# SOTB_Feb22.net
KiCad netlist of a schematic drawn in EAGLE
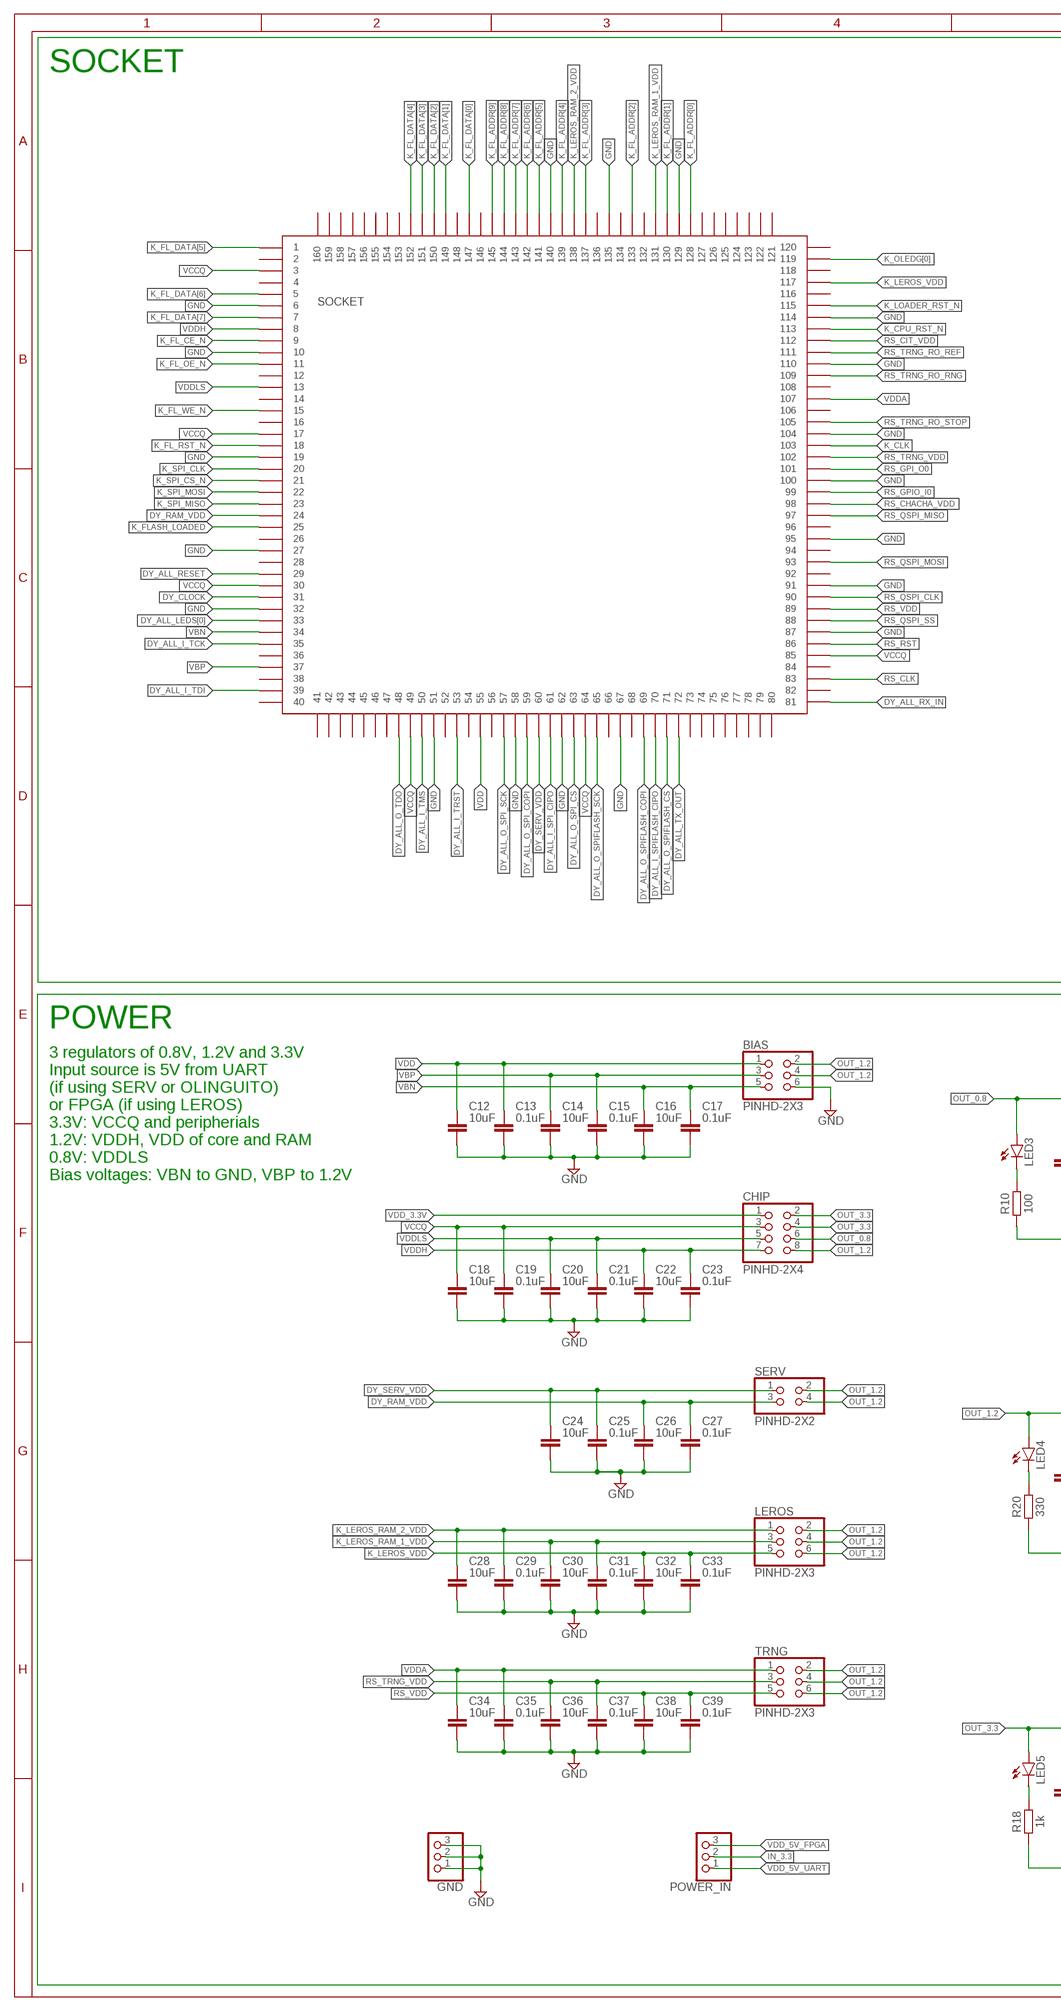
[diagram p0: schematic, sheet 1, part 1 of 2]
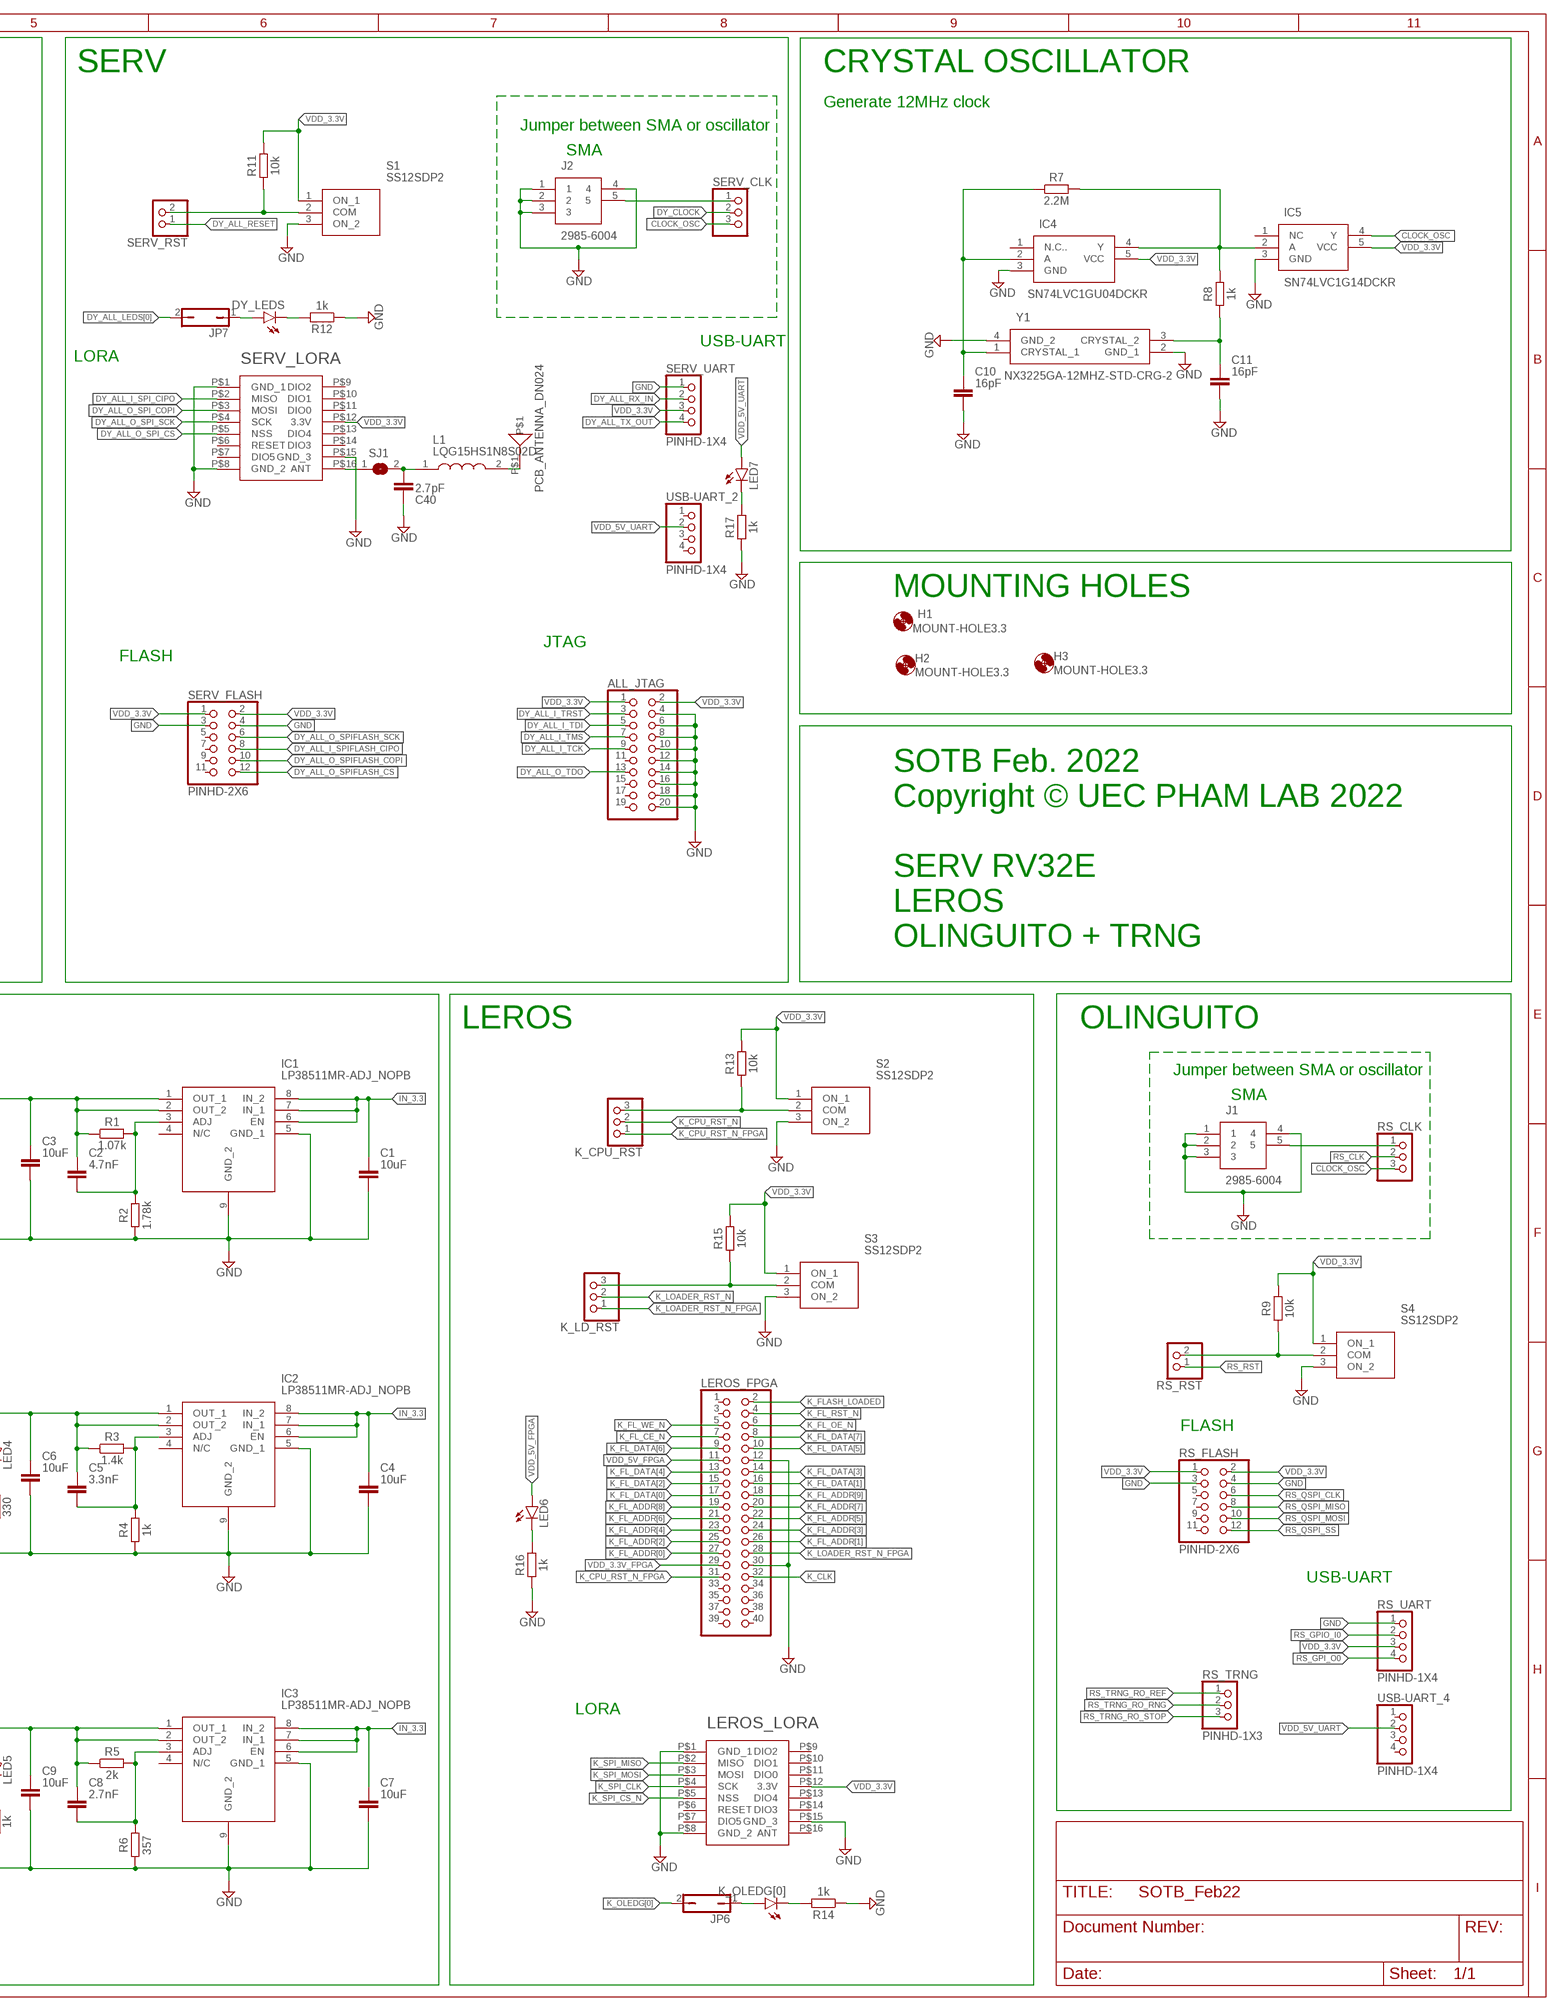
[diagram p1: schematic, sheet 1, part 2 of 2]

(export (version "E")
  (design (tool "Eeschema 10.0.6"))
  (components
    (comp (ref "ALL_JTAG")
      (value "PINHD-2X10")
      (footprint "eagle-import:2X10")
      (libsource (lib "eagle-import") (part "PINHD-2X10"))
    )
    (comp (ref "BIAS")
      (value "PINHD-2X3")
      (footprint "eagle-import:2X03")
      (libsource (lib "eagle-import") (part "PINHD-2X3"))
    )
    (comp (ref "C1")
      (value "10uF")
      (footprint "eagle-import:CAPC3216X135")
      (libsource (lib "eagle-import") (part "CCHIP-1206(3216-METRIC)_"))
    )
    (comp (ref "C2")
      (value "4.7nF")
      (footprint "eagle-import:CAPC3216X135")
      (libsource (lib "eagle-import") (part "CCHIP-1206(3216-METRIC)_"))
    )
    (comp (ref "C3")
      (value "10uF")
      (footprint "eagle-import:CAPC3216X135")
      (libsource (lib "eagle-import") (part "CCHIP-1206(3216-METRIC)_"))
    )
    (comp (ref "C4")
      (value "10uF")
      (footprint "eagle-import:CAPC3216X135")
      (libsource (lib "eagle-import") (part "CCHIP-1206(3216-METRIC)_"))
    )
    (comp (ref "C5")
      (value "3.3nF")
      (footprint "eagle-import:CAPC3216X135")
      (libsource (lib "eagle-import") (part "CCHIP-1206(3216-METRIC)_"))
    )
    (comp (ref "C6")
      (value "10uF")
      (footprint "eagle-import:CAPC3216X135")
      (libsource (lib "eagle-import") (part "CCHIP-1206(3216-METRIC)_"))
    )
    (comp (ref "C7")
      (value "10uF")
      (footprint "eagle-import:CAPC3216X135")
      (libsource (lib "eagle-import") (part "CCHIP-1206(3216-METRIC)_"))
    )
    (comp (ref "C8")
      (value "2.7nF")
      (footprint "eagle-import:CAPC3216X135")
      (libsource (lib "eagle-import") (part "CCHIP-1206(3216-METRIC)_"))
    )
    (comp (ref "C9")
      (value "10uF")
      (footprint "eagle-import:CAPC3216X135")
      (libsource (lib "eagle-import") (part "CCHIP-1206(3216-METRIC)_"))
    )
    (comp (ref "C10")
      (value "16pF")
      (footprint "eagle-import:CAPC3216X135")
      (libsource (lib "eagle-import") (part "CCHIP-1206(3216-METRIC)_"))
    )
    (comp (ref "C11")
      (value "16pF")
      (footprint "eagle-import:CAPC3216X135")
      (libsource (lib "eagle-import") (part "CCHIP-1206(3216-METRIC)_"))
    )
    (comp (ref "C12")
      (value "10uF")
      (footprint "eagle-import:CAPC3216X135")
      (libsource (lib "eagle-import") (part "CCHIP-1206(3216-METRIC)_"))
    )
    (comp (ref "C13")
      (value "0.1uF")
      (footprint "eagle-import:CAPC3216X135")
      (libsource (lib "eagle-import") (part "CCHIP-1206(3216-METRIC)_"))
    )
    (comp (ref "C14")
      (value "10uF")
      (footprint "eagle-import:CAPC3216X135")
      (libsource (lib "eagle-import") (part "CCHIP-1206(3216-METRIC)_"))
    )
    (comp (ref "C15")
      (value "0.1uF")
      (footprint "eagle-import:CAPC3216X135")
      (libsource (lib "eagle-import") (part "CCHIP-1206(3216-METRIC)_"))
    )
    (comp (ref "C16")
      (value "10uF")
      (footprint "eagle-import:CAPC3216X135")
      (libsource (lib "eagle-import") (part "CCHIP-1206(3216-METRIC)_"))
    )
    (comp (ref "C17")
      (value "0.1uF")
      (footprint "eagle-import:CAPC3216X135")
      (libsource (lib "eagle-import") (part "CCHIP-1206(3216-METRIC)_"))
    )
    (comp (ref "C18")
      (value "10uF")
      (footprint "eagle-import:CAPC3216X135")
      (libsource (lib "eagle-import") (part "CCHIP-1206(3216-METRIC)_"))
    )
    (comp (ref "C19")
      (value "0.1uF")
      (footprint "eagle-import:CAPC3216X135")
      (libsource (lib "eagle-import") (part "CCHIP-1206(3216-METRIC)_"))
    )
    (comp (ref "C20")
      (value "10uF")
      (footprint "eagle-import:CAPC3216X135")
      (libsource (lib "eagle-import") (part "CCHIP-1206(3216-METRIC)_"))
    )
    (comp (ref "C21")
      (value "0.1uF")
      (footprint "eagle-import:CAPC3216X135")
      (libsource (lib "eagle-import") (part "CCHIP-1206(3216-METRIC)_"))
    )
    (comp (ref "C22")
      (value "10uF")
      (footprint "eagle-import:CAPC3216X135")
      (libsource (lib "eagle-import") (part "CCHIP-1206(3216-METRIC)_"))
    )
    (comp (ref "C23")
      (value "0.1uF")
      (footprint "eagle-import:CAPC3216X135")
      (libsource (lib "eagle-import") (part "CCHIP-1206(3216-METRIC)_"))
    )
    (comp (ref "C24")
      (value "10uF")
      (footprint "eagle-import:CAPC3216X135")
      (libsource (lib "eagle-import") (part "CCHIP-1206(3216-METRIC)_"))
    )
    (comp (ref "C25")
      (value "0.1uF")
      (footprint "eagle-import:CAPC3216X135")
      (libsource (lib "eagle-import") (part "CCHIP-1206(3216-METRIC)_"))
    )
    (comp (ref "C26")
      (value "10uF")
      (footprint "eagle-import:CAPC3216X135")
      (libsource (lib "eagle-import") (part "CCHIP-1206(3216-METRIC)_"))
    )
    (comp (ref "C27")
      (value "0.1uF")
      (footprint "eagle-import:CAPC3216X135")
      (libsource (lib "eagle-import") (part "CCHIP-1206(3216-METRIC)_"))
    )
    (comp (ref "C28")
      (value "10uF")
      (footprint "eagle-import:CAPC3216X135")
      (libsource (lib "eagle-import") (part "CCHIP-1206(3216-METRIC)_"))
    )
    (comp (ref "C29")
      (value "0.1uF")
      (footprint "eagle-import:CAPC3216X135")
      (libsource (lib "eagle-import") (part "CCHIP-1206(3216-METRIC)_"))
    )
    (comp (ref "C30")
      (value "10uF")
      (footprint "eagle-import:CAPC3216X135")
      (libsource (lib "eagle-import") (part "CCHIP-1206(3216-METRIC)_"))
    )
    (comp (ref "C31")
      (value "0.1uF")
      (footprint "eagle-import:CAPC3216X135")
      (libsource (lib "eagle-import") (part "CCHIP-1206(3216-METRIC)_"))
    )
    (comp (ref "C32")
      (value "10uF")
      (footprint "eagle-import:CAPC3216X135")
      (libsource (lib "eagle-import") (part "CCHIP-1206(3216-METRIC)_"))
    )
    (comp (ref "C33")
      (value "0.1uF")
      (footprint "eagle-import:CAPC3216X135")
      (libsource (lib "eagle-import") (part "CCHIP-1206(3216-METRIC)_"))
    )
    (comp (ref "C34")
      (value "10uF")
      (footprint "eagle-import:CAPC3216X135")
      (libsource (lib "eagle-import") (part "CCHIP-1206(3216-METRIC)_"))
    )
    (comp (ref "C35")
      (value "0.1uF")
      (footprint "eagle-import:CAPC3216X135")
      (libsource (lib "eagle-import") (part "CCHIP-1206(3216-METRIC)_"))
    )
    (comp (ref "C36")
      (value "10uF")
      (footprint "eagle-import:CAPC3216X135")
      (libsource (lib "eagle-import") (part "CCHIP-1206(3216-METRIC)_"))
    )
    (comp (ref "C37")
      (value "0.1uF")
      (footprint "eagle-import:CAPC3216X135")
      (libsource (lib "eagle-import") (part "CCHIP-1206(3216-METRIC)_"))
    )
    (comp (ref "C38")
      (value "10uF")
      (footprint "eagle-import:CAPC3216X135")
      (libsource (lib "eagle-import") (part "CCHIP-1206(3216-METRIC)_"))
    )
    (comp (ref "C39")
      (value "0.1uF")
      (footprint "eagle-import:CAPC3216X135")
      (libsource (lib "eagle-import") (part "CCHIP-1206(3216-METRIC)_"))
    )
    (comp (ref "C40")
      (value "2.7pF")
      (footprint "eagle-import:CAPC3216X135")
      (libsource (lib "eagle-import") (part "CCHIP-1206(3216-METRIC)_"))
    )
    (comp (ref "CHIP")
      (value "PINHD-2X4")
      (footprint "eagle-import:2X04")
      (libsource (lib "eagle-import") (part "PINHD-2X4"))
    )
    (comp (ref "DY_LEDS")
      (value "LEDCHIPLED_1206")
      (footprint "eagle-import:CHIPLED_1206")
      (libsource (lib "eagle-import") (part "LEDCHIPLED_1206"))
    )
    (comp (ref "GND")
      (value "PINHD-1X3")
      (footprint "eagle-import:1X03")
      (libsource (lib "eagle-import") (part "pinhead_325_PINHD-1X3"))
    )
    (comp (ref "H1")
      (value "MOUNT-HOLE3.3")
      (footprint "eagle-import:3,3")
      (libsource (lib "eagle-import") (part "MOUNT-HOLE3.3"))
    )
    (comp (ref "H2")
      (value "MOUNT-HOLE3.3")
      (footprint "eagle-import:3,3")
      (libsource (lib "eagle-import") (part "MOUNT-HOLE3.3"))
    )
    (comp (ref "H3")
      (value "MOUNT-HOLE3.3")
      (footprint "eagle-import:3,3")
      (libsource (lib "eagle-import") (part "MOUNT-HOLE3.3"))
    )
    (comp (ref "IC1")
      (value "LP38511MR-ADJ_NOPB")
      (footprint "eagle-import:SOIC127P600X170-9N")
      (fields
        (field (name "ARROW_PART_NUMBER") "LP38511MR-ADJ/NOPB")
        (field (name "MOUSER_PART_NUMBER") "926-38511MR-ADJ/NOPB")
      )
      (libsource (lib "eagle-import") (part "LP38511MR-ADJ_NOPB"))
    )
    (comp (ref "IC2")
      (value "LP38511MR-ADJ_NOPB")
      (footprint "eagle-import:SOIC127P600X170-9N")
      (fields
        (field (name "ARROW_PART_NUMBER") "LP38511MR-ADJ/NOPB")
        (field (name "MOUSER_PART_NUMBER") "926-38511MR-ADJ/NOPB")
      )
      (libsource (lib "eagle-import") (part "LP38511MR-ADJ_NOPB"))
    )
    (comp (ref "IC3")
      (value "LP38511MR-ADJ_NOPB")
      (footprint "eagle-import:SOIC127P600X170-9N")
      (fields
        (field (name "ARROW_PART_NUMBER") "LP38511MR-ADJ/NOPB")
        (field (name "MOUSER_PART_NUMBER") "926-38511MR-ADJ/NOPB")
      )
      (libsource (lib "eagle-import") (part "LP38511MR-ADJ_NOPB"))
    )
    (comp (ref "IC4")
      (value "SN74LVC1GU04DCKR")
      (footprint "eagle-import:SOT65P210X110-5N")
      (fields (field (name "MOUSER_PART_NUMBER") "595-SN74LVC1GU04DCKR"))
      (libsource (lib "eagle-import") (part "SN74LVC1GU04DCKR"))
    )
    (comp (ref "IC5")
      (value "SN74LVC1G14DCKR")
      (footprint "eagle-import:SOT65P210X110-5N")
      (fields (field (name "MOUSER_PART_NUMBER") "595-SN74LVC1G14DCKR"))
      (libsource (lib "eagle-import") (part "SN74LVC1G14DCKR"))
    )
    (comp (ref "J1")
      (value "2985-6004")
      (footprint "eagle-import:29856004")
      (fields (field (name "MOUSER_PART_NUMBER") "523-2985-6004"))
      (libsource (lib "eagle-import") (part "2985-6004"))
    )
    (comp (ref "J2")
      (value "2985-6004")
      (footprint "eagle-import:29856004")
      (fields (field (name "MOUSER_PART_NUMBER") "523-2985-6004"))
      (libsource (lib "eagle-import") (part "2985-6004"))
    )
    (comp (ref "JP6")
      (value "JP1Q")
      (footprint "eagle-import:JP1")
      (libsource (lib "eagle-import") (part "JP1Q"))
    )
    (comp (ref "JP7")
      (value "JP1Q")
      (footprint "eagle-import:JP1")
      (libsource (lib "eagle-import") (part "JP1Q"))
    )
    (comp (ref "K_CPU_RST")
      (value "PINHD-1X3")
      (footprint "eagle-import:1X03")
      (libsource (lib "eagle-import") (part "pinhead_325_PINHD-1X3"))
    )
    (comp (ref "K_LD_RST")
      (value "PINHD-1X3")
      (footprint "eagle-import:1X03")
      (libsource (lib "eagle-import") (part "pinhead_325_PINHD-1X3"))
    )
    (comp (ref "K_OLEDG[0]")
      (value "LEDCHIPLED_1206")
      (footprint "eagle-import:CHIPLED_1206")
      (libsource (lib "eagle-import") (part "LEDCHIPLED_1206"))
    )
    (comp (ref "L1")
      (value "LQG15HS1N8S02D")
      (footprint "eagle-import:LQG15WH0N7B02D")
      (fields (field (name "MOUSER_PART_NUMBER") "81-LQG15HS1N8S02D"))
      (libsource (lib "eagle-import") (part "LQG15HS1N8S02D"))
    )
    (comp (ref "LED3")
      (value "LEDCHIPLED_1206")
      (footprint "eagle-import:CHIPLED_1206")
      (libsource (lib "eagle-import") (part "LEDCHIPLED_1206"))
    )
    (comp (ref "LED4")
      (value "LEDCHIPLED_1206")
      (footprint "eagle-import:CHIPLED_1206")
      (libsource (lib "eagle-import") (part "LEDCHIPLED_1206"))
    )
    (comp (ref "LED5")
      (value "LEDCHIPLED_1206")
      (footprint "eagle-import:CHIPLED_1206")
      (libsource (lib "eagle-import") (part "LEDCHIPLED_1206"))
    )
    (comp (ref "LED6")
      (value "LEDCHIPLED_1206")
      (footprint "eagle-import:CHIPLED_1206")
      (libsource (lib "eagle-import") (part "LEDCHIPLED_1206"))
    )
    (comp (ref "LED7")
      (value "LEDCHIPLED_1206")
      (footprint "eagle-import:CHIPLED_1206")
      (libsource (lib "eagle-import") (part "LEDCHIPLED_1206"))
    )
    (comp (ref "LEROS")
      (value "PINHD-2X3")
      (footprint "eagle-import:2X03")
      (libsource (lib "eagle-import") (part "PINHD-2X3"))
    )
    (comp (ref "LEROS_FPGA")
      (value "PINHD-2X20")
      (footprint "eagle-import:2X20")
      (libsource (lib "eagle-import") (part "PINHD-2X20"))
    )
    (comp (ref "LEROS_LORA")
      (value "RFM95W-915S2")
      (footprint "eagle-import:RFM95W-915S2")
      (libsource (lib "eagle-import") (part "RFM95W-915S2"))
    )
    (comp (ref "POWER_IN")
      (value "PINHD-1X3")
      (footprint "eagle-import:1X03")
      (libsource (lib "eagle-import") (part "pinhead_325_PINHD-1X3"))
    )
    (comp (ref "R1")
      (value "1.07k")
      (footprint "eagle-import:RESC3216X70")
      (libsource (lib "eagle-import") (part "RCHIP-1206(3216-METRIC)_"))
    )
    (comp (ref "R2")
      (value "1.78k")
      (footprint "eagle-import:RESC3216X70")
      (libsource (lib "eagle-import") (part "RCHIP-1206(3216-METRIC)_"))
    )
    (comp (ref "R3")
      (value "1.4k")
      (footprint "eagle-import:RESC3216X70")
      (libsource (lib "eagle-import") (part "RCHIP-1206(3216-METRIC)_"))
    )
    (comp (ref "R4")
      (value "1k")
      (footprint "eagle-import:RESC3216X70")
      (libsource (lib "eagle-import") (part "RCHIP-1206(3216-METRIC)_"))
    )
    (comp (ref "R5")
      (value "2k")
      (footprint "eagle-import:RESC3216X70")
      (libsource (lib "eagle-import") (part "RCHIP-1206(3216-METRIC)_"))
    )
    (comp (ref "R6")
      (value "357")
      (footprint "eagle-import:RESC3216X70")
      (libsource (lib "eagle-import") (part "RCHIP-1206(3216-METRIC)_"))
    )
    (comp (ref "R7")
      (value "2.2M")
      (footprint "eagle-import:RESC3216X70")
      (libsource (lib "eagle-import") (part "RCHIP-1206(3216-METRIC)_"))
    )
    (comp (ref "R8")
      (value "1k")
      (footprint "eagle-import:RESC3216X70")
      (libsource (lib "eagle-import") (part "RCHIP-1206(3216-METRIC)_"))
    )
    (comp (ref "R9")
      (value "10k")
      (footprint "eagle-import:RESC3216X70")
      (libsource (lib "eagle-import") (part "RCHIP-1206(3216-METRIC)_"))
    )
    (comp (ref "R10")
      (value "100")
      (footprint "eagle-import:RESC3216X70")
      (libsource (lib "eagle-import") (part "RCHIP-1206(3216-METRIC)_"))
    )
    (comp (ref "R11")
      (value "10k")
      (footprint "eagle-import:RESC3216X70")
      (libsource (lib "eagle-import") (part "RCHIP-1206(3216-METRIC)_"))
    )
    (comp (ref "R12")
      (value "1k")
      (footprint "eagle-import:RESC3216X70")
      (libsource (lib "eagle-import") (part "RCHIP-1206(3216-METRIC)_"))
    )
    (comp (ref "R13")
      (value "10k")
      (footprint "eagle-import:RESC3216X70")
      (libsource (lib "eagle-import") (part "RCHIP-1206(3216-METRIC)_"))
    )
    (comp (ref "R14")
      (value "1k")
      (footprint "eagle-import:RESC3216X70")
      (libsource (lib "eagle-import") (part "RCHIP-1206(3216-METRIC)_"))
    )
    (comp (ref "R15")
      (value "10k")
      (footprint "eagle-import:RESC3216X70")
      (libsource (lib "eagle-import") (part "RCHIP-1206(3216-METRIC)_"))
    )
    (comp (ref "R16")
      (value "1k")
      (footprint "eagle-import:RESC3216X70")
      (libsource (lib "eagle-import") (part "RCHIP-1206(3216-METRIC)_"))
    )
    (comp (ref "R17")
      (value "1k")
      (footprint "eagle-import:RESC3216X70")
      (libsource (lib "eagle-import") (part "RCHIP-1206(3216-METRIC)_"))
    )
    (comp (ref "R18")
      (value "1k")
      (footprint "eagle-import:RESC3216X70")
      (libsource (lib "eagle-import") (part "RCHIP-1206(3216-METRIC)_"))
    )
    (comp (ref "R20")
      (value "330")
      (footprint "eagle-import:RESC3216X70")
      (libsource (lib "eagle-import") (part "RCHIP-1206(3216-METRIC)_"))
    )
    (comp (ref "RS_CLK")
      (value "PINHD-1X3")
      (footprint "eagle-import:1X03")
      (libsource (lib "eagle-import") (part "pinhead_325_PINHD-1X3"))
    )
    (comp (ref "RS_FLASH")
      (value "PINHD-2X6")
      (footprint "eagle-import:2X06")
      (libsource (lib "eagle-import") (part "PINHD-2X6"))
    )
    (comp (ref "RS_RST")
      (value "PINHD-1X2")
      (footprint "eagle-import:1X02")
      (libsource (lib "eagle-import") (part "PINHD-1X2"))
    )
    (comp (ref "RS_TRNG")
      (value "PINHD-1X3")
      (footprint "eagle-import:1X03")
      (libsource (lib "eagle-import") (part "PINHD-1X3"))
    )
    (comp (ref "RS_UART")
      (value "PINHD-1X4")
      (footprint "eagle-import:1X04")
      (libsource (lib "eagle-import") (part "PINHD-1X4"))
    )
    (comp (ref "S1")
      (value "SS12SDP2")
      (footprint "eagle-import:SS12SDP2")
      (fields (field (name "MOUSER_PART_NUMBER") "633-SS12SDP2"))
      (libsource (lib "eagle-import") (part "SS12SDP2"))
    )
    (comp (ref "S2")
      (value "SS12SDP2")
      (footprint "eagle-import:SS12SDP2")
      (fields (field (name "MOUSER_PART_NUMBER") "633-SS12SDP2"))
      (libsource (lib "eagle-import") (part "SS12SDP2"))
    )
    (comp (ref "S3")
      (value "SS12SDP2")
      (footprint "eagle-import:SS12SDP2")
      (fields (field (name "MOUSER_PART_NUMBER") "633-SS12SDP2"))
      (libsource (lib "eagle-import") (part "SS12SDP2"))
    )
    (comp (ref "S4")
      (value "SS12SDP2")
      (footprint "eagle-import:SS12SDP2")
      (fields (field (name "MOUSER_PART_NUMBER") "633-SS12SDP2"))
      (libsource (lib "eagle-import") (part "SS12SDP2"))
    )
    (comp (ref "SERV")
      (value "PINHD-2X2")
      (footprint "eagle-import:2X02")
      (libsource (lib "eagle-import") (part "PINHD-2X2"))
    )
    (comp (ref "SERV_CLK")
      (value "PINHD-1X3")
      (footprint "eagle-import:1X03")
      (libsource (lib "eagle-import") (part "pinhead_325_PINHD-1X3"))
    )
    (comp (ref "SERV_FLASH")
      (value "PINHD-2X6")
      (footprint "eagle-import:2X06")
      (libsource (lib "eagle-import") (part "PINHD-2X6"))
    )
    (comp (ref "SERV_LORA")
      (value "RFM95W-915S2")
      (footprint "eagle-import:RFM95W-915S2")
      (libsource (lib "eagle-import") (part "RFM95W-915S2"))
    )
    (comp (ref "SERV_RST")
      (value "PINHD-1X2")
      (footprint "eagle-import:1X02")
      (libsource (lib "eagle-import") (part "PINHD-1X2"))
    )
    (comp (ref "SERV_UART")
      (value "PINHD-1X4")
      (footprint "eagle-import:1X04")
      (libsource (lib "eagle-import") (part "PINHD-1X4"))
    )
    (comp (ref "SJ1") (value "SJ") (footprint "eagle-import:SJ") (libsource (lib "eagle-import") (part "SJ")))
    (comp (ref "SOCKET")
      (value "QFP28-160PIN")
      (footprint "eagle-import:QFP28-160PIN")
      (libsource (lib "eagle-import") (part "QFP28-160PIN"))
    )
    (comp (ref "TRNG")
      (value "PINHD-2X3")
      (footprint "eagle-import:2X03")
      (libsource (lib "eagle-import") (part "PINHD-2X3"))
    )
    (comp (ref "U$1")
      (value "868MHZA_ANTENNA_DN024")
      (footprint "eagle-import:868MHZ_ANTENNA_DN024")
      (libsource (lib "eagle-import") (part "868MHZA_ANTENNA_DN024"))
    )
    (comp (ref "USB-UART_2")
      (value "PINHD-1X4")
      (footprint "eagle-import:1X04")
      (libsource (lib "eagle-import") (part "PINHD-1X4"))
    )
    (comp (ref "USB-UART_4")
      (value "PINHD-1X4")
      (footprint "eagle-import:1X04")
      (libsource (lib "eagle-import") (part "PINHD-1X4"))
    )
    (comp (ref "Y1")
      (value "NX3225GA-12MHZ-STD-CRG-2")
      (footprint "eagle-import:NX3225GA12MHZSTDCRG2")
      (fields (field (name "MOUSER_PART_NUMBER") "344-NX3225GA12STCRG2"))
      (libsource (lib "eagle-import") (part "NX3225GA-12MHZ-STD-CRG-2"))
    )
  )
  (nets
    (net (code "1") (name "CLOCK_OSC") (class "Default")
      (node (ref "IC5") (pin "4") (pinfunction "Y_4") (pintype "bidirectional"))
      (node (ref "RS_CLK") (pin "3") (pinfunction "3_3") (pintype "passive"))
      (node (ref "SERV_CLK") (pin "3") (pinfunction "3_3") (pintype "passive"))
    )
    (net (code "2") (name "DY_ALL_I_SPIFLASH_CIPO") (class "Default")
      (node (ref "SERV_FLASH") (pin "8") (pinfunction "8_8") (pintype "passive"))
      (node (ref "SOCKET") (pin "P$70") (pinfunction "70_P$70") (pintype "bidirectional"))
    )
    (net (code "3") (name "DY_ALL_I_SPI_CIPO") (class "Default")
      (node (ref "SERV_LORA") (pin "P$2") (pinfunction "MISO_P$2") (pintype "bidirectional"))
      (node (ref "SOCKET") (pin "P$61") (pinfunction "61_P$61") (pintype "bidirectional"))
    )
    (net (code "4") (name "DY_ALL_I_TCK") (class "Default")
      (node (ref "ALL_JTAG") (pin "9") (pinfunction "9_9") (pintype "passive"))
      (node (ref "SOCKET") (pin "P$35") (pinfunction "35_P$35") (pintype "bidirectional"))
    )
    (net (code "5") (name "DY_ALL_I_TDI") (class "Default")
      (node (ref "ALL_JTAG") (pin "5") (pinfunction "5_5") (pintype "passive"))
      (node (ref "SOCKET") (pin "P$39") (pinfunction "39_P$39") (pintype "bidirectional"))
    )
    (net (code "6") (name "DY_ALL_I_TMS") (class "Default")
      (node (ref "ALL_JTAG") (pin "7") (pinfunction "7_7") (pintype "passive"))
      (node (ref "SOCKET") (pin "P$50") (pinfunction "50_P$50") (pintype "bidirectional"))
    )
    (net (code "7") (name "DY_ALL_I_TRST") (class "Default")
      (node (ref "ALL_JTAG") (pin "3") (pinfunction "3_3") (pintype "passive"))
      (node (ref "SOCKET") (pin "P$53") (pinfunction "53_P$53") (pintype "bidirectional"))
    )
    (net (code "8") (name "DY_ALL_LEDS[0]") (class "Default")
      (node (ref "JP7") (pin "2") (pinfunction "2_2") (pintype "passive"))
      (node (ref "SOCKET") (pin "P$33") (pinfunction "33_P$33") (pintype "bidirectional"))
    )
    (net (code "9") (name "DY_ALL_O_SPIFLASH_COPI") (class "Default")
      (node (ref "SERV_FLASH") (pin "10") (pinfunction "10_10") (pintype "passive"))
      (node (ref "SOCKET") (pin "P$69") (pinfunction "69_P$69") (pintype "bidirectional"))
    )
    (net (code "10") (name "DY_ALL_O_SPIFLASH_CS") (class "Default")
      (node (ref "SERV_FLASH") (pin "12") (pinfunction "12_12") (pintype "passive"))
      (node (ref "SOCKET") (pin "P$71") (pinfunction "71_P$71") (pintype "bidirectional"))
    )
    (net (code "11") (name "DY_ALL_O_SPIFLASH_SCK") (class "Default")
      (node (ref "SERV_FLASH") (pin "6") (pinfunction "6_6") (pintype "passive"))
      (node (ref "SOCKET") (pin "P$65") (pinfunction "65_P$65") (pintype "bidirectional"))
    )
    (net (code "12") (name "DY_ALL_O_SPI_COPI") (class "Default")
      (node (ref "SERV_LORA") (pin "P$3") (pinfunction "MOSI_P$3") (pintype "bidirectional"))
      (node (ref "SOCKET") (pin "P$59") (pinfunction "59_P$59") (pintype "bidirectional"))
    )
    (net (code "13") (name "DY_ALL_O_SPI_CS") (class "Default")
      (node (ref "SERV_LORA") (pin "P$5") (pinfunction "NSS_P$5") (pintype "bidirectional"))
      (node (ref "SOCKET") (pin "P$63") (pinfunction "63_P$63") (pintype "bidirectional"))
    )
    (net (code "14") (name "DY_ALL_O_SPI_SCK") (class "Default")
      (node (ref "SERV_LORA") (pin "P$4") (pinfunction "SCK_P$4") (pintype "bidirectional"))
      (node (ref "SOCKET") (pin "P$57") (pinfunction "57_P$57") (pintype "bidirectional"))
    )
    (net (code "15") (name "DY_ALL_O_TDO") (class "Default")
      (node (ref "ALL_JTAG") (pin "13") (pinfunction "13_13") (pintype "passive"))
      (node (ref "SOCKET") (pin "P$48") (pinfunction "48_P$48") (pintype "bidirectional"))
    )
    (net (code "16") (name "DY_ALL_RESET") (class "Default")
      (node (ref "SERV_RST") (pin "1") (pinfunction "1_1") (pintype "passive"))
      (node (ref "SOCKET") (pin "P$29") (pinfunction "29_P$29") (pintype "bidirectional"))
    )
    (net (code "17") (name "DY_ALL_RX_IN") (class "Default")
      (node (ref "SERV_UART") (pin "2") (pinfunction "2_2") (pintype "passive"))
      (node (ref "SOCKET") (pin "P$81") (pinfunction "81_P$81") (pintype "bidirectional"))
    )
    (net (code "18") (name "DY_ALL_TX_OUT") (class "Default")
      (node (ref "SERV_UART") (pin "4") (pinfunction "4_4") (pintype "passive"))
      (node (ref "SOCKET") (pin "P$72") (pinfunction "72_P$72") (pintype "bidirectional"))
    )
    (net (code "19") (name "DY_CLOCK") (class "Default")
      (node (ref "SERV_CLK") (pin "2") (pinfunction "2_2") (pintype "passive"))
      (node (ref "SOCKET") (pin "P$31") (pinfunction "31_P$31") (pintype "bidirectional"))
    )
    (net (code "20") (name "DY_RAM_VDD") (class "Default")
      (node (ref "C26") (pin "1") (pinfunction "1_1") (pintype "passive"))
      (node (ref "C27") (pin "1") (pinfunction "1_1") (pintype "passive"))
      (node (ref "SERV") (pin "3") (pinfunction "3_3") (pintype "passive"))
      (node (ref "SOCKET") (pin "P$24") (pinfunction "24_P$24") (pintype "bidirectional"))
    )
    (net (code "21") (name "DY_SERV_VDD") (class "Default")
      (node (ref "C24") (pin "1") (pinfunction "1_1") (pintype "passive"))
      (node (ref "C25") (pin "1") (pinfunction "1_1") (pintype "passive"))
      (node (ref "SERV") (pin "1") (pinfunction "1_1") (pintype "passive"))
      (node (ref "SOCKET") (pin "P$60") (pinfunction "60_P$60") (pintype "bidirectional"))
    )
    (net (code "22") (name "GND") (class "Default")
      (node (ref "ALL_JTAG") (pin "10") (pinfunction "10_10") (pintype "passive"))
      (node (ref "ALL_JTAG") (pin "12") (pinfunction "12_12") (pintype "passive"))
      (node (ref "ALL_JTAG") (pin "14") (pinfunction "14_14") (pintype "passive"))
      (node (ref "ALL_JTAG") (pin "16") (pinfunction "16_16") (pintype "passive"))
      (node (ref "ALL_JTAG") (pin "18") (pinfunction "18_18") (pintype "passive"))
      (node (ref "ALL_JTAG") (pin "20") (pinfunction "20_20") (pintype "passive"))
      (node (ref "ALL_JTAG") (pin "4") (pinfunction "4_4") (pintype "passive"))
      (node (ref "ALL_JTAG") (pin "6") (pinfunction "6_6") (pintype "passive"))
      (node (ref "ALL_JTAG") (pin "8") (pinfunction "8_8") (pintype "passive"))
      (node (ref "BIAS") (pin "6") (pinfunction "6_6") (pintype "passive"))
      (node (ref "C1") (pin "2") (pinfunction "2_2") (pintype "passive"))
      (node (ref "C10") (pin "2") (pinfunction "2_2") (pintype "passive"))
      (node (ref "C11") (pin "2") (pinfunction "2_2") (pintype "passive"))
      (node (ref "C12") (pin "2") (pinfunction "2_2") (pintype "passive"))
      (node (ref "C13") (pin "2") (pinfunction "2_2") (pintype "passive"))
      (node (ref "C14") (pin "2") (pinfunction "2_2") (pintype "passive"))
      (node (ref "C15") (pin "2") (pinfunction "2_2") (pintype "passive"))
      (node (ref "C16") (pin "2") (pinfunction "2_2") (pintype "passive"))
      (node (ref "C17") (pin "2") (pinfunction "2_2") (pintype "passive"))
      (node (ref "C18") (pin "2") (pinfunction "2_2") (pintype "passive"))
      (node (ref "C19") (pin "2") (pinfunction "2_2") (pintype "passive"))
      (node (ref "C20") (pin "2") (pinfunction "2_2") (pintype "passive"))
      (node (ref "C21") (pin "2") (pinfunction "2_2") (pintype "passive"))
      (node (ref "C22") (pin "2") (pinfunction "2_2") (pintype "passive"))
      (node (ref "C23") (pin "2") (pinfunction "2_2") (pintype "passive"))
      (node (ref "C24") (pin "2") (pinfunction "2_2") (pintype "passive"))
      (node (ref "C25") (pin "2") (pinfunction "2_2") (pintype "passive"))
      (node (ref "C26") (pin "2") (pinfunction "2_2") (pintype "passive"))
      (node (ref "C27") (pin "2") (pinfunction "2_2") (pintype "passive"))
      (node (ref "C28") (pin "2") (pinfunction "2_2") (pintype "passive"))
      (node (ref "C29") (pin "2") (pinfunction "2_2") (pintype "passive"))
      (node (ref "C3") (pin "2") (pinfunction "2_2") (pintype "passive"))
      (node (ref "C30") (pin "2") (pinfunction "2_2") (pintype "passive"))
      (node (ref "C31") (pin "2") (pinfunction "2_2") (pintype "passive"))
      (node (ref "C32") (pin "2") (pinfunction "2_2") (pintype "passive"))
      (node (ref "C33") (pin "2") (pinfunction "2_2") (pintype "passive"))
      (node (ref "C34") (pin "2") (pinfunction "2_2") (pintype "passive"))
      (node (ref "C35") (pin "2") (pinfunction "2_2") (pintype "passive"))
      (node (ref "C36") (pin "2") (pinfunction "2_2") (pintype "passive"))
      (node (ref "C37") (pin "2") (pinfunction "2_2") (pintype "passive"))
      (node (ref "C38") (pin "2") (pinfunction "2_2") (pintype "passive"))
      (node (ref "C39") (pin "2") (pinfunction "2_2") (pintype "passive"))
      (node (ref "C4") (pin "2") (pinfunction "2_2") (pintype "passive"))
      (node (ref "C40") (pin "2") (pinfunction "2_2") (pintype "passive"))
      (node (ref "C6") (pin "2") (pinfunction "2_2") (pintype "passive"))
      (node (ref "C7") (pin "2") (pinfunction "2_2") (pintype "passive"))
      (node (ref "C9") (pin "2") (pinfunction "2_2") (pintype "passive"))
      (node (ref "GND") (pin "1") (pinfunction "1_1") (pintype "passive"))
      (node (ref "GND") (pin "2") (pinfunction "2_2") (pintype "passive"))
      (node (ref "GND") (pin "3") (pinfunction "3_3") (pintype "passive"))
      (node (ref "IC1") (pin "5") (pinfunction "GND_1_5") (pintype "bidirectional"))
      (node (ref "IC1") (pin "9") (pinfunction "GND_2_9") (pintype "bidirectional"))
      (node (ref "IC2") (pin "5") (pinfunction "GND_1_5") (pintype "bidirectional"))
      (node (ref "IC2") (pin "9") (pinfunction "GND_2_9") (pintype "bidirectional"))
      (node (ref "IC3") (pin "5") (pinfunction "GND_1_5") (pintype "bidirectional"))
      (node (ref "IC3") (pin "9") (pinfunction "GND_2_9") (pintype "bidirectional"))
      (node (ref "IC4") (pin "3") (pinfunction "GND_3") (pintype "bidirectional"))
      (node (ref "IC5") (pin "3") (pinfunction "GND_3") (pintype "power_in"))
      (node (ref "J1") (pin "1") (pinfunction "1_1") (pintype "bidirectional"))
      (node (ref "J1") (pin "2") (pinfunction "2_2") (pintype "bidirectional"))
      (node (ref "J1") (pin "3") (pinfunction "3_3") (pintype "bidirectional"))
      (node (ref "J1") (pin "4") (pinfunction "4_4") (pintype "bidirectional"))
      (node (ref "J2") (pin "1") (pinfunction "1_1") (pintype "bidirectional"))
      (node (ref "J2") (pin "2") (pinfunction "2_2") (pintype "bidirectional"))
      (node (ref "J2") (pin "3") (pinfunction "3_3") (pintype "bidirectional"))
      (node (ref "J2") (pin "4") (pinfunction "4_4") (pintype "bidirectional"))
      (node (ref "LEROS_FPGA") (pin "12") (pinfunction "12_12") (pintype "passive"))
      (node (ref "LEROS_FPGA") (pin "30") (pinfunction "30_30") (pintype "passive"))
      (node (ref "LEROS_LORA") (pin "P$1") (pinfunction "GND_1_P$1") (pintype "bidirectional"))
      (node (ref "LEROS_LORA") (pin "P$15") (pinfunction "GND_3_P$15") (pintype "bidirectional"))
      (node (ref "LEROS_LORA") (pin "P$8") (pinfunction "GND_2_P$8") (pintype "bidirectional"))
      (node (ref "R10") (pin "1") (pinfunction "1_1") (pintype "passive"))
      (node (ref "R12") (pin "1") (pinfunction "1_1") (pintype "passive"))
      (node (ref "R14") (pin "1") (pinfunction "1_1") (pintype "passive"))
      (node (ref "R16") (pin "1") (pinfunction "1_1") (pintype "passive"))
      (node (ref "R17") (pin "1") (pinfunction "1_1") (pintype "passive"))
      (node (ref "R18") (pin "1") (pinfunction "1_1") (pintype "passive"))
      (node (ref "R2") (pin "1") (pinfunction "1_1") (pintype "passive"))
      (node (ref "R20") (pin "1") (pinfunction "1_1") (pintype "passive"))
      (node (ref "R4") (pin "1") (pinfunction "1_1") (pintype "passive"))
      (node (ref "R6") (pin "1") (pinfunction "1_1") (pintype "passive"))
      (node (ref "RS_FLASH") (pin "3") (pinfunction "3_3") (pintype "passive"))
      (node (ref "RS_FLASH") (pin "4") (pinfunction "4_4") (pintype "passive"))
      (node (ref "RS_UART") (pin "1") (pinfunction "1_1") (pintype "passive"))
      (node (ref "S1") (pin "3") (pinfunction "ON_2_3") (pintype "bidirectional"))
      (node (ref "S2") (pin "3") (pinfunction "ON_2_3") (pintype "bidirectional"))
      (node (ref "S3") (pin "3") (pinfunction "ON_2_3") (pintype "bidirectional"))
      (node (ref "S4") (pin "3") (pinfunction "ON_2_3") (pintype "bidirectional"))
      (node (ref "SERV_FLASH") (pin "3") (pinfunction "3_3") (pintype "passive"))
      (node (ref "SERV_FLASH") (pin "4") (pinfunction "4_4") (pintype "passive"))
      (node (ref "SERV_LORA") (pin "P$1") (pinfunction "GND_1_P$1") (pintype "bidirectional"))
      (node (ref "SERV_LORA") (pin "P$15") (pinfunction "GND_3_P$15") (pintype "bidirectional"))
      (node (ref "SERV_LORA") (pin "P$8") (pinfunction "GND_2_P$8") (pintype "bidirectional"))
      (node (ref "SERV_UART") (pin "1") (pinfunction "1_1") (pintype "passive"))
      (node (ref "SOCKET") (pin "P$10") (pinfunction "10_P$10") (pintype "bidirectional"))
      (node (ref "SOCKET") (pin "P$100") (pinfunction "100_P$100") (pintype "bidirectional"))
      (node (ref "SOCKET") (pin "P$104") (pinfunction "104_P$104") (pintype "bidirectional"))
      (node (ref "SOCKET") (pin "P$110") (pinfunction "110_P$110") (pintype "bidirectional"))
      (node (ref "SOCKET") (pin "P$114") (pinfunction "114_P$114") (pintype "bidirectional"))
      (node (ref "SOCKET") (pin "P$129") (pinfunction "129_P$129") (pintype "bidirectional"))
      (node (ref "SOCKET") (pin "P$135") (pinfunction "135_P$135") (pintype "bidirectional"))
      (node (ref "SOCKET") (pin "P$140") (pinfunction "140_P$140") (pintype "bidirectional"))
      (node (ref "SOCKET") (pin "P$19") (pinfunction "19_P$19") (pintype "bidirectional"))
      (node (ref "SOCKET") (pin "P$27") (pinfunction "27_P$27") (pintype "bidirectional"))
      (node (ref "SOCKET") (pin "P$32") (pinfunction "32_P$32") (pintype "bidirectional"))
      (node (ref "SOCKET") (pin "P$51") (pinfunction "51_P$51") (pintype "bidirectional"))
      (node (ref "SOCKET") (pin "P$58") (pinfunction "58_P$58") (pintype "bidirectional"))
      (node (ref "SOCKET") (pin "P$6") (pinfunction "6_P$6") (pintype "bidirectional"))
      (node (ref "SOCKET") (pin "P$62") (pinfunction "62_P$62") (pintype "bidirectional"))
      (node (ref "SOCKET") (pin "P$67") (pinfunction "67_P$67") (pintype "bidirectional"))
      (node (ref "SOCKET") (pin "P$87") (pinfunction "87_P$87") (pintype "bidirectional"))
      (node (ref "SOCKET") (pin "P$91") (pinfunction "91_P$91") (pintype "bidirectional"))
      (node (ref "SOCKET") (pin "P$95") (pinfunction "95_P$95") (pintype "bidirectional"))
      (node (ref "Y1") (pin "2") (pinfunction "GND_1_2") (pintype "bidirectional"))
      (node (ref "Y1") (pin "4") (pinfunction "GND_2_4") (pintype "bidirectional"))
    )
    (net (code "23") (name "IN_3.3") (class "Default")
      (node (ref "C1") (pin "1") (pinfunction "1_1") (pintype "passive"))
      (node (ref "C4") (pin "1") (pinfunction "1_1") (pintype "passive"))
      (node (ref "C7") (pin "1") (pinfunction "1_1") (pintype "passive"))
      (node (ref "IC1") (pin "6") (pinfunction "EN_6") (pintype "bidirectional"))
      (node (ref "IC1") (pin "7") (pinfunction "IN_1_7") (pintype "bidirectional"))
      (node (ref "IC1") (pin "8") (pinfunction "IN_2_8") (pintype "bidirectional"))
      (node (ref "IC2") (pin "6") (pinfunction "EN_6") (pintype "bidirectional"))
      (node (ref "IC2") (pin "7") (pinfunction "IN_1_7") (pintype "bidirectional"))
      (node (ref "IC2") (pin "8") (pinfunction "IN_2_8") (pintype "bidirectional"))
      (node (ref "IC3") (pin "6") (pinfunction "EN_6") (pintype "bidirectional"))
      (node (ref "IC3") (pin "7") (pinfunction "IN_1_7") (pintype "bidirectional"))
      (node (ref "IC3") (pin "8") (pinfunction "IN_2_8") (pintype "bidirectional"))
      (node (ref "POWER_IN") (pin "2") (pinfunction "2_2") (pintype "passive"))
    )
    (net (code "24") (name "K_CLK") (class "Default")
      (node (ref "LEROS_FPGA") (pin "32") (pinfunction "32_32") (pintype "passive"))
      (node (ref "SOCKET") (pin "P$103") (pinfunction "103_P$103") (pintype "bidirectional"))
    )
    (net (code "25") (name "K_CPU_RST_N") (class "Default")
      (node (ref "K_CPU_RST") (pin "2") (pinfunction "2_2") (pintype "passive"))
      (node (ref "SOCKET") (pin "P$113") (pinfunction "113_P$113") (pintype "bidirectional"))
    )
    (net (code "26") (name "K_CPU_RST_N_FPGA") (class "Default")
      (node (ref "K_CPU_RST") (pin "1") (pinfunction "1_1") (pintype "passive"))
      (node (ref "LEROS_FPGA") (pin "31") (pinfunction "31_31") (pintype "passive"))
    )
    (net (code "27") (name "K_FLASH_LOADED") (class "Default")
      (node (ref "LEROS_FPGA") (pin "2") (pinfunction "2_2") (pintype "passive"))
      (node (ref "SOCKET") (pin "P$25") (pinfunction "25_P$25") (pintype "bidirectional"))
    )
    (net (code "28") (name "K_FL_ADDR[0]") (class "Default")
      (node (ref "LEROS_FPGA") (pin "27") (pinfunction "27_27") (pintype "passive"))
      (node (ref "SOCKET") (pin "P$128") (pinfunction "128_P$128") (pintype "bidirectional"))
    )
    (net (code "29") (name "K_FL_ADDR[1]") (class "Default")
      (node (ref "LEROS_FPGA") (pin "26") (pinfunction "26_26") (pintype "passive"))
      (node (ref "SOCKET") (pin "P$130") (pinfunction "130_P$130") (pintype "bidirectional"))
    )
    (net (code "30") (name "K_FL_ADDR[2]") (class "Default")
      (node (ref "LEROS_FPGA") (pin "25") (pinfunction "25_25") (pintype "passive"))
      (node (ref "SOCKET") (pin "P$133") (pinfunction "133_P$133") (pintype "bidirectional"))
    )
    (net (code "31") (name "K_FL_ADDR[3]") (class "Default")
      (node (ref "LEROS_FPGA") (pin "24") (pinfunction "24_24") (pintype "passive"))
      (node (ref "SOCKET") (pin "P$137") (pinfunction "137_P$137") (pintype "bidirectional"))
    )
    (net (code "32") (name "K_FL_ADDR[4]") (class "Default")
      (node (ref "LEROS_FPGA") (pin "23") (pinfunction "23_23") (pintype "passive"))
      (node (ref "SOCKET") (pin "P$139") (pinfunction "139_P$139") (pintype "bidirectional"))
    )
    (net (code "33") (name "K_FL_ADDR[5]") (class "Default")
      (node (ref "LEROS_FPGA") (pin "22") (pinfunction "22_22") (pintype "passive"))
      (node (ref "SOCKET") (pin "P$141") (pinfunction "141_P$141") (pintype "bidirectional"))
    )
    (net (code "34") (name "K_FL_ADDR[6]") (class "Default")
      (node (ref "LEROS_FPGA") (pin "21") (pinfunction "21_21") (pintype "passive"))
      (node (ref "SOCKET") (pin "P$142") (pinfunction "142_P$142") (pintype "bidirectional"))
    )
    (net (code "35") (name "K_FL_ADDR[7]") (class "Default")
      (node (ref "LEROS_FPGA") (pin "20") (pinfunction "20_20") (pintype "passive"))
      (node (ref "SOCKET") (pin "P$143") (pinfunction "143_P$143") (pintype "bidirectional"))
    )
    (net (code "36") (name "K_FL_ADDR[8]") (class "Default")
      (node (ref "LEROS_FPGA") (pin "19") (pinfunction "19_19") (pintype "passive"))
      (node (ref "SOCKET") (pin "P$144") (pinfunction "144_P$144") (pintype "bidirectional"))
    )
    (net (code "37") (name "K_FL_ADDR[9]") (class "Default")
      (node (ref "LEROS_FPGA") (pin "18") (pinfunction "18_18") (pintype "passive"))
      (node (ref "SOCKET") (pin "P$145") (pinfunction "145_P$145") (pintype "bidirectional"))
    )
    (net (code "38") (name "K_FL_CE_N") (class "Default")
      (node (ref "LEROS_FPGA") (pin "7") (pinfunction "7_7") (pintype "passive"))
      (node (ref "SOCKET") (pin "P$9") (pinfunction "9_P$9") (pintype "bidirectional"))
    )
    (net (code "39") (name "K_FL_DATA[0]") (class "Default")
      (node (ref "LEROS_FPGA") (pin "17") (pinfunction "17_17") (pintype "passive"))
      (node (ref "SOCKET") (pin "P$147") (pinfunction "147_P$147") (pintype "bidirectional"))
    )
    (net (code "40") (name "K_FL_DATA[1]") (class "Default")
      (node (ref "LEROS_FPGA") (pin "16") (pinfunction "16_16") (pintype "passive"))
      (node (ref "SOCKET") (pin "P$149") (pinfunction "149_P$149") (pintype "bidirectional"))
    )
    (net (code "41") (name "K_FL_DATA[2]") (class "Default")
      (node (ref "LEROS_FPGA") (pin "15") (pinfunction "15_15") (pintype "passive"))
      (node (ref "SOCKET") (pin "P$150") (pinfunction "150_P$150") (pintype "bidirectional"))
    )
    (net (code "42") (name "K_FL_DATA[3]") (class "Default")
      (node (ref "LEROS_FPGA") (pin "14") (pinfunction "14_14") (pintype "passive"))
      (node (ref "SOCKET") (pin "P$151") (pinfunction "151_P$151") (pintype "bidirectional"))
    )
    (net (code "43") (name "K_FL_DATA[4]") (class "Default")
      (node (ref "LEROS_FPGA") (pin "13") (pinfunction "13_13") (pintype "passive"))
      (node (ref "SOCKET") (pin "P$152") (pinfunction "152_P$152") (pintype "bidirectional"))
    )
    (net (code "44") (name "K_FL_DATA[5]") (class "Default")
      (node (ref "LEROS_FPGA") (pin "10") (pinfunction "10_10") (pintype "passive"))
      (node (ref "SOCKET") (pin "P$1") (pinfunction "1_P$1") (pintype "bidirectional"))
    )
    (net (code "45") (name "K_FL_DATA[6]") (class "Default")
      (node (ref "LEROS_FPGA") (pin "9") (pinfunction "9_9") (pintype "passive"))
      (node (ref "SOCKET") (pin "P$5") (pinfunction "5_P$5") (pintype "bidirectional"))
    )
    (net (code "46") (name "K_FL_DATA[7]") (class "Default")
      (node (ref "LEROS_FPGA") (pin "8") (pinfunction "8_8") (pintype "passive"))
      (node (ref "SOCKET") (pin "P$7") (pinfunction "7_P$7") (pintype "bidirectional"))
    )
    (net (code "47") (name "K_FL_OE_N") (class "Default")
      (node (ref "LEROS_FPGA") (pin "6") (pinfunction "6_6") (pintype "passive"))
      (node (ref "SOCKET") (pin "P$11") (pinfunction "11_P$11") (pintype "bidirectional"))
    )
    (net (code "48") (name "K_FL_RST_N") (class "Default")
      (node (ref "LEROS_FPGA") (pin "4") (pinfunction "4_4") (pintype "passive"))
      (node (ref "SOCKET") (pin "P$18") (pinfunction "18_P$18") (pintype "bidirectional"))
    )
    (net (code "49") (name "K_FL_WE_N") (class "Default")
      (node (ref "LEROS_FPGA") (pin "5") (pinfunction "5_5") (pintype "passive"))
      (node (ref "SOCKET") (pin "P$15") (pinfunction "15_P$15") (pintype "bidirectional"))
    )
    (net (code "50") (name "K_LEROS_RAM_1_VDD") (class "Default")
      (node (ref "C30") (pin "1") (pinfunction "1_1") (pintype "passive"))
      (node (ref "C31") (pin "1") (pinfunction "1_1") (pintype "passive"))
      (node (ref "LEROS") (pin "3") (pinfunction "3_3") (pintype "passive"))
      (node (ref "SOCKET") (pin "P$131") (pinfunction "131_P$131") (pintype "bidirectional"))
    )
    (net (code "51") (name "K_LEROS_RAM_2_VDD") (class "Default")
      (node (ref "C28") (pin "1") (pinfunction "1_1") (pintype "passive"))
      (node (ref "C29") (pin "1") (pinfunction "1_1") (pintype "passive"))
      (node (ref "LEROS") (pin "1") (pinfunction "1_1") (pintype "passive"))
      (node (ref "SOCKET") (pin "P$138") (pinfunction "138_P$138") (pintype "bidirectional"))
    )
    (net (code "52") (name "K_LEROS_VDD") (class "Default")
      (node (ref "C32") (pin "1") (pinfunction "1_1") (pintype "passive"))
      (node (ref "C33") (pin "1") (pinfunction "1_1") (pintype "passive"))
      (node (ref "LEROS") (pin "5") (pinfunction "5_5") (pintype "passive"))
      (node (ref "SOCKET") (pin "P$117") (pinfunction "117_P$117") (pintype "bidirectional"))
    )
    (net (code "53") (name "K_LOADER_RST_N") (class "Default")
      (node (ref "K_LD_RST") (pin "2") (pinfunction "2_2") (pintype "passive"))
      (node (ref "SOCKET") (pin "P$115") (pinfunction "115_P$115") (pintype "bidirectional"))
    )
    (net (code "54") (name "K_LOADER_RST_N_FPGA") (class "Default")
      (node (ref "K_LD_RST") (pin "1") (pinfunction "1_1") (pintype "passive"))
      (node (ref "LEROS_FPGA") (pin "28") (pinfunction "28_28") (pintype "passive"))
    )
    (net (code "55") (name "K_OLEDG[0]") (class "Default")
      (node (ref "JP6") (pin "2") (pinfunction "2_2") (pintype "passive"))
      (node (ref "SOCKET") (pin "P$119") (pinfunction "119_P$119") (pintype "bidirectional"))
    )
    (net (code "56") (name "K_SPI_CLK") (class "Default")
      (node (ref "LEROS_LORA") (pin "P$4") (pinfunction "SCK_P$4") (pintype "bidirectional"))
      (node (ref "SOCKET") (pin "P$20") (pinfunction "20_P$20") (pintype "bidirectional"))
    )
    (net (code "57") (name "K_SPI_CS_N") (class "Default")
      (node (ref "LEROS_LORA") (pin "P$5") (pinfunction "NSS_P$5") (pintype "bidirectional"))
      (node (ref "SOCKET") (pin "P$21") (pinfunction "21_P$21") (pintype "bidirectional"))
    )
    (net (code "58") (name "K_SPI_MISO") (class "Default")
      (node (ref "LEROS_LORA") (pin "P$2") (pinfunction "MISO_P$2") (pintype "bidirectional"))
      (node (ref "SOCKET") (pin "P$23") (pinfunction "23_P$23") (pintype "bidirectional"))
    )
    (net (code "59") (name "K_SPI_MOSI") (class "Default")
      (node (ref "LEROS_LORA") (pin "P$3") (pinfunction "MOSI_P$3") (pintype "bidirectional"))
      (node (ref "SOCKET") (pin "P$22") (pinfunction "22_P$22") (pintype "bidirectional"))
    )
    (net (code "60") (name "Net-(C40-Pad1)") (class "Default")
      (node (ref "C40") (pin "1") (pinfunction "1_1") (pintype "passive"))
      (node (ref "L1") (pin "1") (pinfunction "1_1") (pintype "bidirectional"))
      (node (ref "SJ1") (pin "2") (pinfunction "2_2") (pintype "passive"))
    )
    (net (code "61") (name "Net-(DY_LEDS-PadA)") (class "Default")
      (node (ref "DY_LEDS") (pin "A") (pinfunction "A_A") (pintype "passive"))
      (node (ref "JP7") (pin "1") (pinfunction "1_1") (pintype "passive"))
    )
    (net (code "62") (name "Net-(DY_LEDS-PadC)") (class "Default")
      (node (ref "DY_LEDS") (pin "C") (pinfunction "C_C") (pintype "passive"))
      (node (ref "R12") (pin "2") (pinfunction "2_2") (pintype "passive"))
    )
    (net (code "63") (name "Net-(IC1-ADJ)") (class "Default")
      (node (ref "C2") (pin "2") (pinfunction "2_2") (pintype "passive"))
      (node (ref "IC1") (pin "3") (pinfunction "ADJ_3") (pintype "bidirectional"))
      (node (ref "R1") (pin "2") (pinfunction "2_2") (pintype "passive"))
      (node (ref "R2") (pin "2") (pinfunction "2_2") (pintype "passive"))
    )
    (net (code "64") (name "Net-(IC2-ADJ)") (class "Default")
      (node (ref "C5") (pin "2") (pinfunction "2_2") (pintype "passive"))
      (node (ref "IC2") (pin "3") (pinfunction "ADJ_3") (pintype "bidirectional"))
      (node (ref "R3") (pin "2") (pinfunction "2_2") (pintype "passive"))
      (node (ref "R4") (pin "2") (pinfunction "2_2") (pintype "passive"))
    )
    (net (code "65") (name "Net-(IC3-ADJ)") (class "Default")
      (node (ref "C8") (pin "2") (pinfunction "2_2") (pintype "passive"))
      (node (ref "IC3") (pin "3") (pinfunction "ADJ_3") (pintype "bidirectional"))
      (node (ref "R5") (pin "2") (pinfunction "2_2") (pintype "passive"))
      (node (ref "R6") (pin "2") (pinfunction "2_2") (pintype "passive"))
    )
    (net (code "66") (name "Net-(IC4-A)") (class "Default")
      (node (ref "C10") (pin "1") (pinfunction "1_1") (pintype "passive"))
      (node (ref "IC4") (pin "2") (pinfunction "A_2") (pintype "bidirectional"))
      (node (ref "R7") (pin "1") (pinfunction "1_1") (pintype "passive"))
      (node (ref "Y1") (pin "1") (pinfunction "CRYSTAL_1_1") (pintype "bidirectional"))
    )
    (net (code "67") (name "Net-(IC4-Y)") (class "Default")
      (node (ref "IC4") (pin "4") (pinfunction "Y_4") (pintype "bidirectional"))
      (node (ref "IC5") (pin "2") (pinfunction "A_2") (pintype "bidirectional"))
      (node (ref "R7") (pin "2") (pinfunction "2_2") (pintype "passive"))
      (node (ref "R8") (pin "2") (pinfunction "2_2") (pintype "passive"))
    )
    (net (code "68") (name "Net-(J1-Pad5)") (class "Default")
      (node (ref "J1") (pin "5") (pinfunction "5_5") (pintype "bidirectional"))
      (node (ref "RS_CLK") (pin "1") (pinfunction "1_1") (pintype "passive"))
    )
    (net (code "69") (name "Net-(J2-Pad5)") (class "Default")
      (node (ref "J2") (pin "5") (pinfunction "5_5") (pintype "bidirectional"))
      (node (ref "SERV_CLK") (pin "1") (pinfunction "1_1") (pintype "passive"))
    )
    (net (code "70") (name "Net-(JP6-Pad1)") (class "Default")
      (node (ref "JP6") (pin "1") (pinfunction "1_1") (pintype "passive"))
      (node (ref "K_OLEDG[0]") (pin "A") (pinfunction "A_A") (pintype "passive"))
    )
    (net (code "71") (name "Net-(K_OLEDG[0]-PadC)") (class "Default")
      (node (ref "K_OLEDG[0]") (pin "C") (pinfunction "C_C") (pintype "passive"))
      (node (ref "R14") (pin "2") (pinfunction "2_2") (pintype "passive"))
    )
    (net (code "72") (name "Net-(L1-Pad2)") (class "Default")
      (node (ref "L1") (pin "2") (pinfunction "2_2") (pintype "bidirectional"))
      (node (ref "U$1") (pin "P$1") (pinfunction "P$1_P$1") (pintype "bidirectional"))
    )
    (net (code "73") (name "Net-(LED3-PadC)") (class "Default")
      (node (ref "LED3") (pin "C") (pinfunction "C_C") (pintype "passive"))
      (node (ref "R10") (pin "2") (pinfunction "2_2") (pintype "passive"))
    )
    (net (code "74") (name "Net-(LED4-PadC)") (class "Default")
      (node (ref "LED4") (pin "C") (pinfunction "C_C") (pintype "passive"))
      (node (ref "R20") (pin "2") (pinfunction "2_2") (pintype "passive"))
    )
    (net (code "75") (name "Net-(LED5-PadC)") (class "Default")
      (node (ref "LED5") (pin "C") (pinfunction "C_C") (pintype "passive"))
      (node (ref "R18") (pin "2") (pinfunction "2_2") (pintype "passive"))
    )
    (net (code "76") (name "Net-(LED6-PadC)") (class "Default")
      (node (ref "LED6") (pin "C") (pinfunction "C_C") (pintype "passive"))
      (node (ref "R16") (pin "2") (pinfunction "2_2") (pintype "passive"))
    )
    (net (code "77") (name "Net-(LED7-PadC)") (class "Default")
      (node (ref "LED7") (pin "C") (pinfunction "C_C") (pintype "passive"))
      (node (ref "R17") (pin "2") (pinfunction "2_2") (pintype "passive"))
    )
    (net (code "78") (name "Net-(S1-COM)") (class "Default")
      (node (ref "R11") (pin "1") (pinfunction "1_1") (pintype "passive"))
      (node (ref "S1") (pin "2") (pinfunction "COM_2") (pintype "bidirectional"))
      (node (ref "SERV_RST") (pin "2") (pinfunction "2_2") (pintype "passive"))
    )
    (net (code "79") (name "Net-(S2-COM)") (class "Default")
      (node (ref "K_CPU_RST") (pin "3") (pinfunction "3_3") (pintype "passive"))
      (node (ref "R13") (pin "1") (pinfunction "1_1") (pintype "passive"))
      (node (ref "S2") (pin "2") (pinfunction "COM_2") (pintype "bidirectional"))
    )
    (net (code "80") (name "Net-(S3-COM)") (class "Default")
      (node (ref "K_LD_RST") (pin "3") (pinfunction "3_3") (pintype "passive"))
      (node (ref "R15") (pin "1") (pinfunction "1_1") (pintype "passive"))
      (node (ref "S3") (pin "2") (pinfunction "COM_2") (pintype "bidirectional"))
    )
    (net (code "81") (name "Net-(S4-COM)") (class "Default")
      (node (ref "R9") (pin "1") (pinfunction "1_1") (pintype "passive"))
      (node (ref "RS_RST") (pin "2") (pinfunction "2_2") (pintype "passive"))
      (node (ref "S4") (pin "2") (pinfunction "COM_2") (pintype "bidirectional"))
    )
    (net (code "82") (name "Net-(SERV_LORA-ANT)") (class "Default")
      (node (ref "SERV_LORA") (pin "P$16") (pinfunction "ANT_P$16") (pintype "bidirectional"))
      (node (ref "SJ1") (pin "1") (pinfunction "1_1") (pintype "passive"))
    )
    (net (code "83") (name "Net-(Y1-CRYSTAL_2)") (class "Default")
      (node (ref "C11") (pin "1") (pinfunction "1_1") (pintype "passive"))
      (node (ref "R8") (pin "1") (pinfunction "1_1") (pintype "passive"))
      (node (ref "Y1") (pin "3") (pinfunction "CRYSTAL_2_3") (pintype "bidirectional"))
    )
    (net (code "84") (name "OUT_0.8") (class "Default")
      (node (ref "C2") (pin "1") (pinfunction "1_1") (pintype "passive"))
      (node (ref "C3") (pin "1") (pinfunction "1_1") (pintype "passive"))
      (node (ref "CHIP") (pin "6") (pinfunction "6_6") (pintype "passive"))
      (node (ref "IC1") (pin "1") (pinfunction "OUT_1_1") (pintype "bidirectional"))
      (node (ref "IC1") (pin "2") (pinfunction "OUT_2_2") (pintype "bidirectional"))
      (node (ref "LED3") (pin "A") (pinfunction "A_A") (pintype "passive"))
      (node (ref "R1") (pin "1") (pinfunction "1_1") (pintype "passive"))
    )
    (net (code "85") (name "OUT_1.2") (class "Default")
      (node (ref "BIAS") (pin "2") (pinfunction "2_2") (pintype "passive"))
      (node (ref "BIAS") (pin "4") (pinfunction "4_4") (pintype "passive"))
      (node (ref "C5") (pin "1") (pinfunction "1_1") (pintype "passive"))
      (node (ref "C6") (pin "1") (pinfunction "1_1") (pintype "passive"))
      (node (ref "CHIP") (pin "8") (pinfunction "8_8") (pintype "passive"))
      (node (ref "IC2") (pin "1") (pinfunction "OUT_1_1") (pintype "bidirectional"))
      (node (ref "IC2") (pin "2") (pinfunction "OUT_2_2") (pintype "bidirectional"))
      (node (ref "LED4") (pin "A") (pinfunction "A_A") (pintype "passive"))
      (node (ref "LEROS") (pin "2") (pinfunction "2_2") (pintype "passive"))
      (node (ref "LEROS") (pin "4") (pinfunction "4_4") (pintype "passive"))
      (node (ref "LEROS") (pin "6") (pinfunction "6_6") (pintype "passive"))
      (node (ref "R3") (pin "1") (pinfunction "1_1") (pintype "passive"))
      (node (ref "SERV") (pin "2") (pinfunction "2_2") (pintype "passive"))
      (node (ref "SERV") (pin "4") (pinfunction "4_4") (pintype "passive"))
      (node (ref "TRNG") (pin "2") (pinfunction "2_2") (pintype "passive"))
      (node (ref "TRNG") (pin "4") (pinfunction "4_4") (pintype "passive"))
      (node (ref "TRNG") (pin "6") (pinfunction "6_6") (pintype "passive"))
    )
    (net (code "86") (name "OUT_3.3") (class "Default")
      (node (ref "C8") (pin "1") (pinfunction "1_1") (pintype "passive"))
      (node (ref "C9") (pin "1") (pinfunction "1_1") (pintype "passive"))
      (node (ref "CHIP") (pin "2") (pinfunction "2_2") (pintype "passive"))
      (node (ref "CHIP") (pin "4") (pinfunction "4_4") (pintype "passive"))
      (node (ref "IC3") (pin "1") (pinfunction "OUT_1_1") (pintype "bidirectional"))
      (node (ref "IC3") (pin "2") (pinfunction "OUT_2_2") (pintype "bidirectional"))
      (node (ref "LED5") (pin "A") (pinfunction "A_A") (pintype "passive"))
      (node (ref "R5") (pin "1") (pinfunction "1_1") (pintype "passive"))
    )
    (net (code "87") (name "RS_CHACHA_VDD") (class "Default")
      (node (ref "SOCKET") (pin "P$98") (pinfunction "98_P$98") (pintype "bidirectional"))
    )
    (net (code "88") (name "RS_CIT_VDD") (class "Default")
      (node (ref "SOCKET") (pin "P$112") (pinfunction "112_P$112") (pintype "bidirectional"))
    )
    (net (code "89") (name "RS_CLK") (class "Default")
      (node (ref "RS_CLK") (pin "2") (pinfunction "2_2") (pintype "passive"))
      (node (ref "SOCKET") (pin "P$83") (pinfunction "83_P$83") (pintype "bidirectional"))
    )
    (net (code "90") (name "RS_GPIO_I0") (class "Default")
      (node (ref "RS_UART") (pin "2") (pinfunction "2_2") (pintype "passive"))
      (node (ref "SOCKET") (pin "P$99") (pinfunction "99_P$99") (pintype "bidirectional"))
    )
    (net (code "91") (name "RS_GPI_O0") (class "Default")
      (node (ref "RS_UART") (pin "4") (pinfunction "4_4") (pintype "passive"))
      (node (ref "SOCKET") (pin "P$101") (pinfunction "101_P$101") (pintype "bidirectional"))
    )
    (net (code "92") (name "RS_QSPI_CLK") (class "Default")
      (node (ref "RS_FLASH") (pin "6") (pinfunction "6_6") (pintype "passive"))
      (node (ref "SOCKET") (pin "P$90") (pinfunction "90_P$90") (pintype "bidirectional"))
    )
    (net (code "93") (name "RS_QSPI_MISO") (class "Default")
      (node (ref "RS_FLASH") (pin "8") (pinfunction "8_8") (pintype "passive"))
      (node (ref "SOCKET") (pin "P$97") (pinfunction "97_P$97") (pintype "bidirectional"))
    )
    (net (code "94") (name "RS_QSPI_MOSI") (class "Default")
      (node (ref "RS_FLASH") (pin "10") (pinfunction "10_10") (pintype "passive"))
      (node (ref "SOCKET") (pin "P$93") (pinfunction "93_P$93") (pintype "bidirectional"))
    )
    (net (code "95") (name "RS_QSPI_SS") (class "Default")
      (node (ref "RS_FLASH") (pin "12") (pinfunction "12_12") (pintype "passive"))
      (node (ref "SOCKET") (pin "P$88") (pinfunction "88_P$88") (pintype "bidirectional"))
    )
    (net (code "96") (name "RS_RST") (class "Default")
      (node (ref "RS_RST") (pin "1") (pinfunction "1_1") (pintype "passive"))
      (node (ref "SOCKET") (pin "P$86") (pinfunction "86_P$86") (pintype "bidirectional"))
    )
    (net (code "97") (name "RS_TRNG_RO_REF") (class "Default")
      (node (ref "RS_TRNG") (pin "1") (pinfunction "1_1") (pintype "passive"))
      (node (ref "SOCKET") (pin "P$111") (pinfunction "111_P$111") (pintype "bidirectional"))
    )
    (net (code "98") (name "RS_TRNG_RO_RNG") (class "Default")
      (node (ref "RS_TRNG") (pin "2") (pinfunction "2_2") (pintype "passive"))
      (node (ref "SOCKET") (pin "P$109") (pinfunction "109_P$109") (pintype "bidirectional"))
    )
    (net (code "99") (name "RS_TRNG_RO_STOP") (class "Default")
      (node (ref "RS_TRNG") (pin "3") (pinfunction "3_3") (pintype "passive"))
      (node (ref "SOCKET") (pin "P$105") (pinfunction "105_P$105") (pintype "bidirectional"))
    )
    (net (code "100") (name "RS_TRNG_VDD") (class "Default")
      (node (ref "C36") (pin "1") (pinfunction "1_1") (pintype "passive"))
      (node (ref "C37") (pin "1") (pinfunction "1_1") (pintype "passive"))
      (node (ref "SOCKET") (pin "P$102") (pinfunction "102_P$102") (pintype "bidirectional"))
      (node (ref "TRNG") (pin "3") (pinfunction "3_3") (pintype "passive"))
    )
    (net (code "101") (name "RS_VDD") (class "Default")
      (node (ref "C38") (pin "1") (pinfunction "1_1") (pintype "passive"))
      (node (ref "C39") (pin "1") (pinfunction "1_1") (pintype "passive"))
      (node (ref "SOCKET") (pin "P$89") (pinfunction "89_P$89") (pintype "bidirectional"))
      (node (ref "TRNG") (pin "5") (pinfunction "5_5") (pintype "passive"))
    )
    (net (code "102") (name "VBN") (class "Default")
      (node (ref "BIAS") (pin "5") (pinfunction "5_5") (pintype "passive"))
      (node (ref "C16") (pin "1") (pinfunction "1_1") (pintype "passive"))
      (node (ref "C17") (pin "1") (pinfunction "1_1") (pintype "passive"))
      (node (ref "SOCKET") (pin "P$34") (pinfunction "34_P$34") (pintype "bidirectional"))
    )
    (net (code "103") (name "VBP") (class "Default")
      (node (ref "BIAS") (pin "3") (pinfunction "3_3") (pintype "passive"))
      (node (ref "C14") (pin "1") (pinfunction "1_1") (pintype "passive"))
      (node (ref "C15") (pin "1") (pinfunction "1_1") (pintype "passive"))
      (node (ref "SOCKET") (pin "P$37") (pinfunction "37_P$37") (pintype "bidirectional"))
    )
    (net (code "104") (name "VCCQ") (class "Default")
      (node (ref "C18") (pin "1") (pinfunction "1_1") (pintype "passive"))
      (node (ref "C19") (pin "1") (pinfunction "1_1") (pintype "passive"))
      (node (ref "CHIP") (pin "3") (pinfunction "3_3") (pintype "passive"))
      (node (ref "SOCKET") (pin "P$17") (pinfunction "17_P$17") (pintype "bidirectional"))
      (node (ref "SOCKET") (pin "P$3") (pinfunction "3_P$3") (pintype "bidirectional"))
      (node (ref "SOCKET") (pin "P$30") (pinfunction "30_P$30") (pintype "bidirectional"))
      (node (ref "SOCKET") (pin "P$49") (pinfunction "49_P$49") (pintype "bidirectional"))
      (node (ref "SOCKET") (pin "P$64") (pinfunction "64_P$64") (pintype "bidirectional"))
      (node (ref "SOCKET") (pin "P$85") (pinfunction "85_P$85") (pintype "bidirectional"))
    )
    (net (code "105") (name "VDD") (class "Default")
      (node (ref "BIAS") (pin "1") (pinfunction "1_1") (pintype "passive"))
      (node (ref "C12") (pin "1") (pinfunction "1_1") (pintype "passive"))
      (node (ref "C13") (pin "1") (pinfunction "1_1") (pintype "passive"))
      (node (ref "SOCKET") (pin "P$55") (pinfunction "55_P$55") (pintype "bidirectional"))
    )
    (net (code "106") (name "VDDA") (class "Default")
      (node (ref "C34") (pin "1") (pinfunction "1_1") (pintype "passive"))
      (node (ref "C35") (pin "1") (pinfunction "1_1") (pintype "passive"))
      (node (ref "SOCKET") (pin "P$107") (pinfunction "107_P$107") (pintype "bidirectional"))
      (node (ref "TRNG") (pin "1") (pinfunction "1_1") (pintype "passive"))
    )
    (net (code "107") (name "VDDH") (class "Default")
      (node (ref "C22") (pin "1") (pinfunction "1_1") (pintype "passive"))
      (node (ref "C23") (pin "1") (pinfunction "1_1") (pintype "passive"))
      (node (ref "CHIP") (pin "7") (pinfunction "7_7") (pintype "passive"))
      (node (ref "SOCKET") (pin "P$8") (pinfunction "8_P$8") (pintype "bidirectional"))
    )
    (net (code "108") (name "VDDLS") (class "Default")
      (node (ref "C20") (pin "1") (pinfunction "1_1") (pintype "passive"))
      (node (ref "C21") (pin "1") (pinfunction "1_1") (pintype "passive"))
      (node (ref "CHIP") (pin "5") (pinfunction "5_5") (pintype "passive"))
      (node (ref "SOCKET") (pin "P$13") (pinfunction "13_P$13") (pintype "bidirectional"))
    )
    (net (code "109") (name "VDD_3.3V") (class "Default")
      (node (ref "ALL_JTAG") (pin "1") (pinfunction "1_1") (pintype "passive"))
      (node (ref "ALL_JTAG") (pin "2") (pinfunction "2_2") (pintype "passive"))
      (node (ref "CHIP") (pin "1") (pinfunction "1_1") (pintype "passive"))
      (node (ref "IC4") (pin "5") (pinfunction "VCC_5") (pintype "bidirectional"))
      (node (ref "IC5") (pin "5") (pinfunction "VCC_5") (pintype "power_in"))
      (node (ref "LEROS_LORA") (pin "P$12") (pinfunction "3.3V_P$12") (pintype "bidirectional"))
      (node (ref "R11") (pin "2") (pinfunction "2_2") (pintype "passive"))
      (node (ref "R13") (pin "2") (pinfunction "2_2") (pintype "passive"))
      (node (ref "R15") (pin "2") (pinfunction "2_2") (pintype "passive"))
      (node (ref "R9") (pin "2") (pinfunction "2_2") (pintype "passive"))
      (node (ref "RS_FLASH") (pin "1") (pinfunction "1_1") (pintype "passive"))
      (node (ref "RS_FLASH") (pin "2") (pinfunction "2_2") (pintype "passive"))
      (node (ref "RS_UART") (pin "3") (pinfunction "3_3") (pintype "passive"))
      (node (ref "S1") (pin "1") (pinfunction "ON_1_1") (pintype "bidirectional"))
      (node (ref "S2") (pin "1") (pinfunction "ON_1_1") (pintype "bidirectional"))
      (node (ref "S3") (pin "1") (pinfunction "ON_1_1") (pintype "bidirectional"))
      (node (ref "S4") (pin "1") (pinfunction "ON_1_1") (pintype "bidirectional"))
      (node (ref "SERV_FLASH") (pin "1") (pinfunction "1_1") (pintype "passive"))
      (node (ref "SERV_FLASH") (pin "2") (pinfunction "2_2") (pintype "passive"))
      (node (ref "SERV_LORA") (pin "P$12") (pinfunction "3.3V_P$12") (pintype "bidirectional"))
      (node (ref "SERV_UART") (pin "3") (pinfunction "3_3") (pintype "passive"))
    )
    (net (code "110") (name "VDD_3.3V_FPGA") (class "Default")
      (node (ref "LEROS_FPGA") (pin "29") (pinfunction "29_29") (pintype "passive"))
    )
    (net (code "111") (name "VDD_5V_FPGA") (class "Default")
      (node (ref "LED6") (pin "A") (pinfunction "A_A") (pintype "passive"))
      (node (ref "LEROS_FPGA") (pin "11") (pinfunction "11_11") (pintype "passive"))
      (node (ref "POWER_IN") (pin "3") (pinfunction "3_3") (pintype "passive"))
    )
    (net (code "112") (name "VDD_5V_UART") (class "Default")
      (node (ref "LED7") (pin "A") (pinfunction "A_A") (pintype "passive"))
      (node (ref "POWER_IN") (pin "1") (pinfunction "1_1") (pintype "passive"))
      (node (ref "USB-UART_2") (pin "2") (pinfunction "2_2") (pintype "passive"))
      (node (ref "USB-UART_4") (pin "2") (pinfunction "2_2") (pintype "passive"))
    )
    (net (code "113") (name "unconnected-(ALL_JTAG-Pad11)") (class "Default")
      (node (ref "ALL_JTAG") (pin "11") (pinfunction "11_11") (pintype "passive"))
    )
    (net (code "114") (name "unconnected-(ALL_JTAG-Pad15)") (class "Default")
      (node (ref "ALL_JTAG") (pin "15") (pinfunction "15_15") (pintype "passive"))
    )
    (net (code "115") (name "unconnected-(ALL_JTAG-Pad17)") (class "Default")
      (node (ref "ALL_JTAG") (pin "17") (pinfunction "17_17") (pintype "passive"))
    )
    (net (code "116") (name "unconnected-(ALL_JTAG-Pad19)") (class "Default")
      (node (ref "ALL_JTAG") (pin "19") (pinfunction "19_19") (pintype "passive"))
    )
    (net (code "117") (name "unconnected-(IC1-N{slash}C-Pad4)") (class "Default")
      (node (ref "IC1") (pin "4") (pinfunction "N/C_4") (pintype "no_connect"))
    )
    (net (code "118") (name "unconnected-(IC2-N{slash}C-Pad4)") (class "Default")
      (node (ref "IC2") (pin "4") (pinfunction "N/C_4") (pintype "no_connect"))
    )
    (net (code "119") (name "unconnected-(IC3-N{slash}C-Pad4)") (class "Default")
      (node (ref "IC3") (pin "4") (pinfunction "N/C_4") (pintype "no_connect"))
    )
    (net (code "120") (name "unconnected-(IC4-N.C..-Pad1)") (class "Default")
      (node (ref "IC4") (pin "1") (pinfunction "N.C.._1") (pintype "bidirectional"))
    )
    (net (code "121") (name "unconnected-(IC5-NC-Pad1)") (class "Default")
      (node (ref "IC5") (pin "1") (pinfunction "NC_1") (pintype "no_connect"))
    )
    (net (code "122") (name "unconnected-(LEROS_FPGA-Pad1)") (class "Default")
      (node (ref "LEROS_FPGA") (pin "1") (pinfunction "1_1") (pintype "passive"))
    )
    (net (code "123") (name "unconnected-(LEROS_FPGA-Pad3)") (class "Default")
      (node (ref "LEROS_FPGA") (pin "3") (pinfunction "3_3") (pintype "passive"))
    )
    (net (code "124") (name "unconnected-(LEROS_FPGA-Pad33)") (class "Default")
      (node (ref "LEROS_FPGA") (pin "33") (pinfunction "33_33") (pintype "passive"))
    )
    (net (code "125") (name "unconnected-(LEROS_FPGA-Pad34)") (class "Default")
      (node (ref "LEROS_FPGA") (pin "34") (pinfunction "34_34") (pintype "passive"))
    )
    (net (code "126") (name "unconnected-(LEROS_FPGA-Pad35)") (class "Default")
      (node (ref "LEROS_FPGA") (pin "35") (pinfunction "35_35") (pintype "passive"))
    )
    (net (code "127") (name "unconnected-(LEROS_FPGA-Pad36)") (class "Default")
      (node (ref "LEROS_FPGA") (pin "36") (pinfunction "36_36") (pintype "passive"))
    )
    (net (code "128") (name "unconnected-(LEROS_FPGA-Pad37)") (class "Default")
      (node (ref "LEROS_FPGA") (pin "37") (pinfunction "37_37") (pintype "passive"))
    )
    (net (code "129") (name "unconnected-(LEROS_FPGA-Pad38)") (class "Default")
      (node (ref "LEROS_FPGA") (pin "38") (pinfunction "38_38") (pintype "passive"))
    )
    (net (code "130") (name "unconnected-(LEROS_FPGA-Pad39)") (class "Default")
      (node (ref "LEROS_FPGA") (pin "39") (pinfunction "39_39") (pintype "passive"))
    )
    (net (code "131") (name "unconnected-(LEROS_FPGA-Pad40)") (class "Default")
      (node (ref "LEROS_FPGA") (pin "40") (pinfunction "40_40") (pintype "passive"))
    )
    (net (code "132") (name "unconnected-(LEROS_LORA-ANT-PadP$16)") (class "Default")
      (node (ref "LEROS_LORA") (pin "P$16") (pinfunction "ANT_P$16") (pintype "bidirectional"))
    )
    (net (code "133") (name "unconnected-(LEROS_LORA-DIO0-PadP$11)") (class "Default")
      (node (ref "LEROS_LORA") (pin "P$11") (pinfunction "DIO0_P$11") (pintype "bidirectional"))
    )
    (net (code "134") (name "unconnected-(LEROS_LORA-DIO1-PadP$10)") (class "Default")
      (node (ref "LEROS_LORA") (pin "P$10") (pinfunction "DIO1_P$10") (pintype "bidirectional"))
    )
    (net (code "135") (name "unconnected-(LEROS_LORA-DIO2-PadP$9)") (class "Default")
      (node (ref "LEROS_LORA") (pin "P$9") (pinfunction "DIO2_P$9") (pintype "bidirectional"))
    )
    (net (code "136") (name "unconnected-(LEROS_LORA-DIO3-PadP$14)") (class "Default")
      (node (ref "LEROS_LORA") (pin "P$14") (pinfunction "DIO3_P$14") (pintype "bidirectional"))
    )
    (net (code "137") (name "unconnected-(LEROS_LORA-DIO4-PadP$13)") (class "Default")
      (node (ref "LEROS_LORA") (pin "P$13") (pinfunction "DIO4_P$13") (pintype "bidirectional"))
    )
    (net (code "138") (name "unconnected-(LEROS_LORA-DIO5-PadP$7)") (class "Default")
      (node (ref "LEROS_LORA") (pin "P$7") (pinfunction "DIO5_P$7") (pintype "bidirectional"))
    )
    (net (code "139") (name "unconnected-(LEROS_LORA-RESET-PadP$6)") (class "Default")
      (node (ref "LEROS_LORA") (pin "P$6") (pinfunction "RESET_P$6") (pintype "bidirectional"))
    )
    (net (code "140") (name "unconnected-(RS_FLASH-Pad5)") (class "Default")
      (node (ref "RS_FLASH") (pin "5") (pinfunction "5_5") (pintype "passive"))
    )
    (net (code "141") (name "unconnected-(RS_FLASH-Pad7)") (class "Default")
      (node (ref "RS_FLASH") (pin "7") (pinfunction "7_7") (pintype "passive"))
    )
    (net (code "142") (name "unconnected-(RS_FLASH-Pad9)") (class "Default")
      (node (ref "RS_FLASH") (pin "9") (pinfunction "9_9") (pintype "passive"))
    )
    (net (code "143") (name "unconnected-(RS_FLASH-Pad11)") (class "Default")
      (node (ref "RS_FLASH") (pin "11") (pinfunction "11_11") (pintype "passive"))
    )
    (net (code "144") (name "unconnected-(SERV_FLASH-Pad5)") (class "Default")
      (node (ref "SERV_FLASH") (pin "5") (pinfunction "5_5") (pintype "passive"))
    )
    (net (code "145") (name "unconnected-(SERV_FLASH-Pad7)") (class "Default")
      (node (ref "SERV_FLASH") (pin "7") (pinfunction "7_7") (pintype "passive"))
    )
    (net (code "146") (name "unconnected-(SERV_FLASH-Pad9)") (class "Default")
      (node (ref "SERV_FLASH") (pin "9") (pinfunction "9_9") (pintype "passive"))
    )
    (net (code "147") (name "unconnected-(SERV_FLASH-Pad11)") (class "Default")
      (node (ref "SERV_FLASH") (pin "11") (pinfunction "11_11") (pintype "passive"))
    )
    (net (code "148") (name "unconnected-(SERV_LORA-DIO0-PadP$11)") (class "Default")
      (node (ref "SERV_LORA") (pin "P$11") (pinfunction "DIO0_P$11") (pintype "bidirectional"))
    )
    (net (code "149") (name "unconnected-(SERV_LORA-DIO1-PadP$10)") (class "Default")
      (node (ref "SERV_LORA") (pin "P$10") (pinfunction "DIO1_P$10") (pintype "bidirectional"))
    )
    (net (code "150") (name "unconnected-(SERV_LORA-DIO2-PadP$9)") (class "Default")
      (node (ref "SERV_LORA") (pin "P$9") (pinfunction "DIO2_P$9") (pintype "bidirectional"))
    )
    (net (code "151") (name "unconnected-(SERV_LORA-DIO3-PadP$14)") (class "Default")
      (node (ref "SERV_LORA") (pin "P$14") (pinfunction "DIO3_P$14") (pintype "bidirectional"))
    )
    (net (code "152") (name "unconnected-(SERV_LORA-DIO4-PadP$13)") (class "Default")
      (node (ref "SERV_LORA") (pin "P$13") (pinfunction "DIO4_P$13") (pintype "bidirectional"))
    )
    (net (code "153") (name "unconnected-(SERV_LORA-DIO5-PadP$7)") (class "Default")
      (node (ref "SERV_LORA") (pin "P$7") (pinfunction "DIO5_P$7") (pintype "bidirectional"))
    )
    (net (code "154") (name "unconnected-(SERV_LORA-RESET-PadP$6)") (class "Default")
      (node (ref "SERV_LORA") (pin "P$6") (pinfunction "RESET_P$6") (pintype "bidirectional"))
    )
    (net (code "155") (name "unconnected-(SOCKET-2-PadP$2)") (class "Default")
      (node (ref "SOCKET") (pin "P$2") (pinfunction "2_P$2") (pintype "bidirectional"))
    )
    (net (code "156") (name "unconnected-(SOCKET-4-PadP$4)") (class "Default")
      (node (ref "SOCKET") (pin "P$4") (pinfunction "4_P$4") (pintype "bidirectional"))
    )
    (net (code "157") (name "unconnected-(SOCKET-12-PadP$12)") (class "Default")
      (node (ref "SOCKET") (pin "P$12") (pinfunction "12_P$12") (pintype "bidirectional"))
    )
    (net (code "158") (name "unconnected-(SOCKET-14-PadP$14)") (class "Default")
      (node (ref "SOCKET") (pin "P$14") (pinfunction "14_P$14") (pintype "bidirectional"))
    )
    (net (code "159") (name "unconnected-(SOCKET-16-PadP$16)") (class "Default")
      (node (ref "SOCKET") (pin "P$16") (pinfunction "16_P$16") (pintype "bidirectional"))
    )
    (net (code "160") (name "unconnected-(SOCKET-26-PadP$26)") (class "Default")
      (node (ref "SOCKET") (pin "P$26") (pinfunction "26_P$26") (pintype "bidirectional"))
    )
    (net (code "161") (name "unconnected-(SOCKET-28-PadP$28)") (class "Default")
      (node (ref "SOCKET") (pin "P$28") (pinfunction "28_P$28") (pintype "bidirectional"))
    )
    (net (code "162") (name "unconnected-(SOCKET-36-PadP$36)") (class "Default")
      (node (ref "SOCKET") (pin "P$36") (pinfunction "36_P$36") (pintype "bidirectional"))
    )
    (net (code "163") (name "unconnected-(SOCKET-38-PadP$38)") (class "Default")
      (node (ref "SOCKET") (pin "P$38") (pinfunction "38_P$38") (pintype "bidirectional"))
    )
    (net (code "164") (name "unconnected-(SOCKET-40-PadP$40)") (class "Default")
      (node (ref "SOCKET") (pin "P$40") (pinfunction "40_P$40") (pintype "bidirectional"))
    )
    (net (code "165") (name "unconnected-(SOCKET-41-PadP$41)") (class "Default")
      (node (ref "SOCKET") (pin "P$41") (pinfunction "41_P$41") (pintype "bidirectional"))
    )
    (net (code "166") (name "unconnected-(SOCKET-42-PadP$42)") (class "Default")
      (node (ref "SOCKET") (pin "P$42") (pinfunction "42_P$42") (pintype "bidirectional"))
    )
    (net (code "167") (name "unconnected-(SOCKET-43-PadP$43)") (class "Default")
      (node (ref "SOCKET") (pin "P$43") (pinfunction "43_P$43") (pintype "bidirectional"))
    )
    (net (code "168") (name "unconnected-(SOCKET-44-PadP$44)") (class "Default")
      (node (ref "SOCKET") (pin "P$44") (pinfunction "44_P$44") (pintype "bidirectional"))
    )
    (net (code "169") (name "unconnected-(SOCKET-45-PadP$45)") (class "Default")
      (node (ref "SOCKET") (pin "P$45") (pinfunction "45_P$45") (pintype "bidirectional"))
    )
    (net (code "170") (name "unconnected-(SOCKET-46-PadP$46)") (class "Default")
      (node (ref "SOCKET") (pin "P$46") (pinfunction "46_P$46") (pintype "bidirectional"))
    )
    (net (code "171") (name "unconnected-(SOCKET-47-PadP$47)") (class "Default")
      (node (ref "SOCKET") (pin "P$47") (pinfunction "47_P$47") (pintype "bidirectional"))
    )
    (net (code "172") (name "unconnected-(SOCKET-52-PadP$52)") (class "Default")
      (node (ref "SOCKET") (pin "P$52") (pinfunction "52_P$52") (pintype "bidirectional"))
    )
    (net (code "173") (name "unconnected-(SOCKET-54-PadP$54)") (class "Default")
      (node (ref "SOCKET") (pin "P$54") (pinfunction "54_P$54") (pintype "bidirectional"))
    )
    (net (code "174") (name "unconnected-(SOCKET-56-PadP$56)") (class "Default")
      (node (ref "SOCKET") (pin "P$56") (pinfunction "56_P$56") (pintype "bidirectional"))
    )
    (net (code "175") (name "unconnected-(SOCKET-66-PadP$66)") (class "Default")
      (node (ref "SOCKET") (pin "P$66") (pinfunction "66_P$66") (pintype "bidirectional"))
    )
    (net (code "176") (name "unconnected-(SOCKET-68-PadP$68)") (class "Default")
      (node (ref "SOCKET") (pin "P$68") (pinfunction "68_P$68") (pintype "bidirectional"))
    )
    (net (code "177") (name "unconnected-(SOCKET-73-PadP$73)") (class "Default")
      (node (ref "SOCKET") (pin "P$73") (pinfunction "73_P$73") (pintype "bidirectional"))
    )
    (net (code "178") (name "unconnected-(SOCKET-74-PadP$74)") (class "Default")
      (node (ref "SOCKET") (pin "P$74") (pinfunction "74_P$74") (pintype "bidirectional"))
    )
    (net (code "179") (name "unconnected-(SOCKET-75-PadP$75)") (class "Default")
      (node (ref "SOCKET") (pin "P$75") (pinfunction "75_P$75") (pintype "bidirectional"))
    )
    (net (code "180") (name "unconnected-(SOCKET-76-PadP$76)") (class "Default")
      (node (ref "SOCKET") (pin "P$76") (pinfunction "76_P$76") (pintype "bidirectional"))
    )
    (net (code "181") (name "unconnected-(SOCKET-77-PadP$77)") (class "Default")
      (node (ref "SOCKET") (pin "P$77") (pinfunction "77_P$77") (pintype "bidirectional"))
    )
    (net (code "182") (name "unconnected-(SOCKET-78-PadP$78)") (class "Default")
      (node (ref "SOCKET") (pin "P$78") (pinfunction "78_P$78") (pintype "bidirectional"))
    )
    (net (code "183") (name "unconnected-(SOCKET-79-PadP$79)") (class "Default")
      (node (ref "SOCKET") (pin "P$79") (pinfunction "79_P$79") (pintype "bidirectional"))
    )
    (net (code "184") (name "unconnected-(SOCKET-80-PadP$80)") (class "Default")
      (node (ref "SOCKET") (pin "P$80") (pinfunction "80_P$80") (pintype "bidirectional"))
    )
    (net (code "185") (name "unconnected-(SOCKET-82-PadP$82)") (class "Default")
      (node (ref "SOCKET") (pin "P$82") (pinfunction "82_P$82") (pintype "bidirectional"))
    )
    (net (code "186") (name "unconnected-(SOCKET-84-PadP$84)") (class "Default")
      (node (ref "SOCKET") (pin "P$84") (pinfunction "84_P$84") (pintype "bidirectional"))
    )
    (net (code "187") (name "unconnected-(SOCKET-92-PadP$92)") (class "Default")
      (node (ref "SOCKET") (pin "P$92") (pinfunction "92_P$92") (pintype "bidirectional"))
    )
    (net (code "188") (name "unconnected-(SOCKET-94-PadP$94)") (class "Default")
      (node (ref "SOCKET") (pin "P$94") (pinfunction "94_P$94") (pintype "bidirectional"))
    )
    (net (code "189") (name "unconnected-(SOCKET-96-PadP$96)") (class "Default")
      (node (ref "SOCKET") (pin "P$96") (pinfunction "96_P$96") (pintype "bidirectional"))
    )
    (net (code "190") (name "unconnected-(SOCKET-106-PadP$106)") (class "Default")
      (node (ref "SOCKET") (pin "P$106") (pinfunction "106_P$106") (pintype "bidirectional"))
    )
    (net (code "191") (name "unconnected-(SOCKET-108-PadP$108)") (class "Default")
      (node (ref "SOCKET") (pin "P$108") (pinfunction "108_P$108") (pintype "bidirectional"))
    )
    (net (code "192") (name "unconnected-(SOCKET-116-PadP$116)") (class "Default")
      (node (ref "SOCKET") (pin "P$116") (pinfunction "116_P$116") (pintype "bidirectional"))
    )
    (net (code "193") (name "unconnected-(SOCKET-118-PadP$118)") (class "Default")
      (node (ref "SOCKET") (pin "P$118") (pinfunction "118_P$118") (pintype "bidirectional"))
    )
    (net (code "194") (name "unconnected-(SOCKET-120-PadP$120)") (class "Default")
      (node (ref "SOCKET") (pin "P$120") (pinfunction "120_P$120") (pintype "bidirectional"))
    )
    (net (code "195") (name "unconnected-(SOCKET-121-PadP$121)") (class "Default")
      (node (ref "SOCKET") (pin "P$121") (pinfunction "121_P$121") (pintype "bidirectional"))
    )
    (net (code "196") (name "unconnected-(SOCKET-122-PadP$122)") (class "Default")
      (node (ref "SOCKET") (pin "P$122") (pinfunction "122_P$122") (pintype "bidirectional"))
    )
    (net (code "197") (name "unconnected-(SOCKET-123-PadP$123)") (class "Default")
      (node (ref "SOCKET") (pin "P$123") (pinfunction "123_P$123") (pintype "bidirectional"))
    )
    (net (code "198") (name "unconnected-(SOCKET-124-PadP$124)") (class "Default")
      (node (ref "SOCKET") (pin "P$124") (pinfunction "124_P$124") (pintype "bidirectional"))
    )
    (net (code "199") (name "unconnected-(SOCKET-125-PadP$125)") (class "Default")
      (node (ref "SOCKET") (pin "P$125") (pinfunction "125_P$125") (pintype "bidirectional"))
    )
    (net (code "200") (name "unconnected-(SOCKET-126-PadP$126)") (class "Default")
      (node (ref "SOCKET") (pin "P$126") (pinfunction "126_P$126") (pintype "bidirectional"))
    )
    (net (code "201") (name "unconnected-(SOCKET-127-PadP$127)") (class "Default")
      (node (ref "SOCKET") (pin "P$127") (pinfunction "127_P$127") (pintype "bidirectional"))
    )
    (net (code "202") (name "unconnected-(SOCKET-132-PadP$132)") (class "Default")
      (node (ref "SOCKET") (pin "P$132") (pinfunction "132_P$132") (pintype "bidirectional"))
    )
    (net (code "203") (name "unconnected-(SOCKET-134-PadP$134)") (class "Default")
      (node (ref "SOCKET") (pin "P$134") (pinfunction "134_P$134") (pintype "bidirectional"))
    )
    (net (code "204") (name "unconnected-(SOCKET-136-PadP$136)") (class "Default")
      (node (ref "SOCKET") (pin "P$136") (pinfunction "136_P$136") (pintype "bidirectional"))
    )
    (net (code "205") (name "unconnected-(SOCKET-146-PadP$146)") (class "Default")
      (node (ref "SOCKET") (pin "P$146") (pinfunction "146_P$146") (pintype "bidirectional"))
    )
    (net (code "206") (name "unconnected-(SOCKET-148-PadP$148)") (class "Default")
      (node (ref "SOCKET") (pin "P$148") (pinfunction "148_P$148") (pintype "bidirectional"))
    )
    (net (code "207") (name "unconnected-(SOCKET-153-PadP$153)") (class "Default")
      (node (ref "SOCKET") (pin "P$153") (pinfunction "153_P$153") (pintype "bidirectional"))
    )
    (net (code "208") (name "unconnected-(SOCKET-154-PadP$154)") (class "Default")
      (node (ref "SOCKET") (pin "P$154") (pinfunction "154_P$154") (pintype "bidirectional"))
    )
    (net (code "209") (name "unconnected-(SOCKET-155-PadP$155)") (class "Default")
      (node (ref "SOCKET") (pin "P$155") (pinfunction "155_P$155") (pintype "bidirectional"))
    )
    (net (code "210") (name "unconnected-(SOCKET-156-PadP$156)") (class "Default")
      (node (ref "SOCKET") (pin "P$156") (pinfunction "156_P$156") (pintype "bidirectional"))
    )
    (net (code "211") (name "unconnected-(SOCKET-157-PadP$157)") (class "Default")
      (node (ref "SOCKET") (pin "P$157") (pinfunction "157_P$157") (pintype "bidirectional"))
    )
    (net (code "212") (name "unconnected-(SOCKET-158-PadP$158)") (class "Default")
      (node (ref "SOCKET") (pin "P$158") (pinfunction "158_P$158") (pintype "bidirectional"))
    )
    (net (code "213") (name "unconnected-(SOCKET-159-PadP$159)") (class "Default")
      (node (ref "SOCKET") (pin "P$159") (pinfunction "159_P$159") (pintype "bidirectional"))
    )
    (net (code "214") (name "unconnected-(SOCKET-160-PadP$160)") (class "Default")
      (node (ref "SOCKET") (pin "P$160") (pinfunction "160_P$160") (pintype "bidirectional"))
    )
    (net (code "215") (name "unconnected-(USB-UART_2-Pad1)") (class "Default")
      (node (ref "USB-UART_2") (pin "1") (pinfunction "1_1") (pintype "passive"))
    )
    (net (code "216") (name "unconnected-(USB-UART_2-Pad3)") (class "Default")
      (node (ref "USB-UART_2") (pin "3") (pinfunction "3_3") (pintype "passive"))
    )
    (net (code "217") (name "unconnected-(USB-UART_2-Pad4)") (class "Default")
      (node (ref "USB-UART_2") (pin "4") (pinfunction "4_4") (pintype "passive"))
    )
    (net (code "218") (name "unconnected-(USB-UART_4-Pad1)") (class "Default")
      (node (ref "USB-UART_4") (pin "1") (pinfunction "1_1") (pintype "passive"))
    )
    (net (code "219") (name "unconnected-(USB-UART_4-Pad3)") (class "Default")
      (node (ref "USB-UART_4") (pin "3") (pinfunction "3_3") (pintype "passive"))
    )
    (net (code "220") (name "unconnected-(USB-UART_4-Pad4)") (class "Default")
      (node (ref "USB-UART_4") (pin "4") (pinfunction "4_4") (pintype "passive"))
    )
  )
)
